# tarjeta-v8.net
KiCad netlist of a schematic drawn in EAGLE
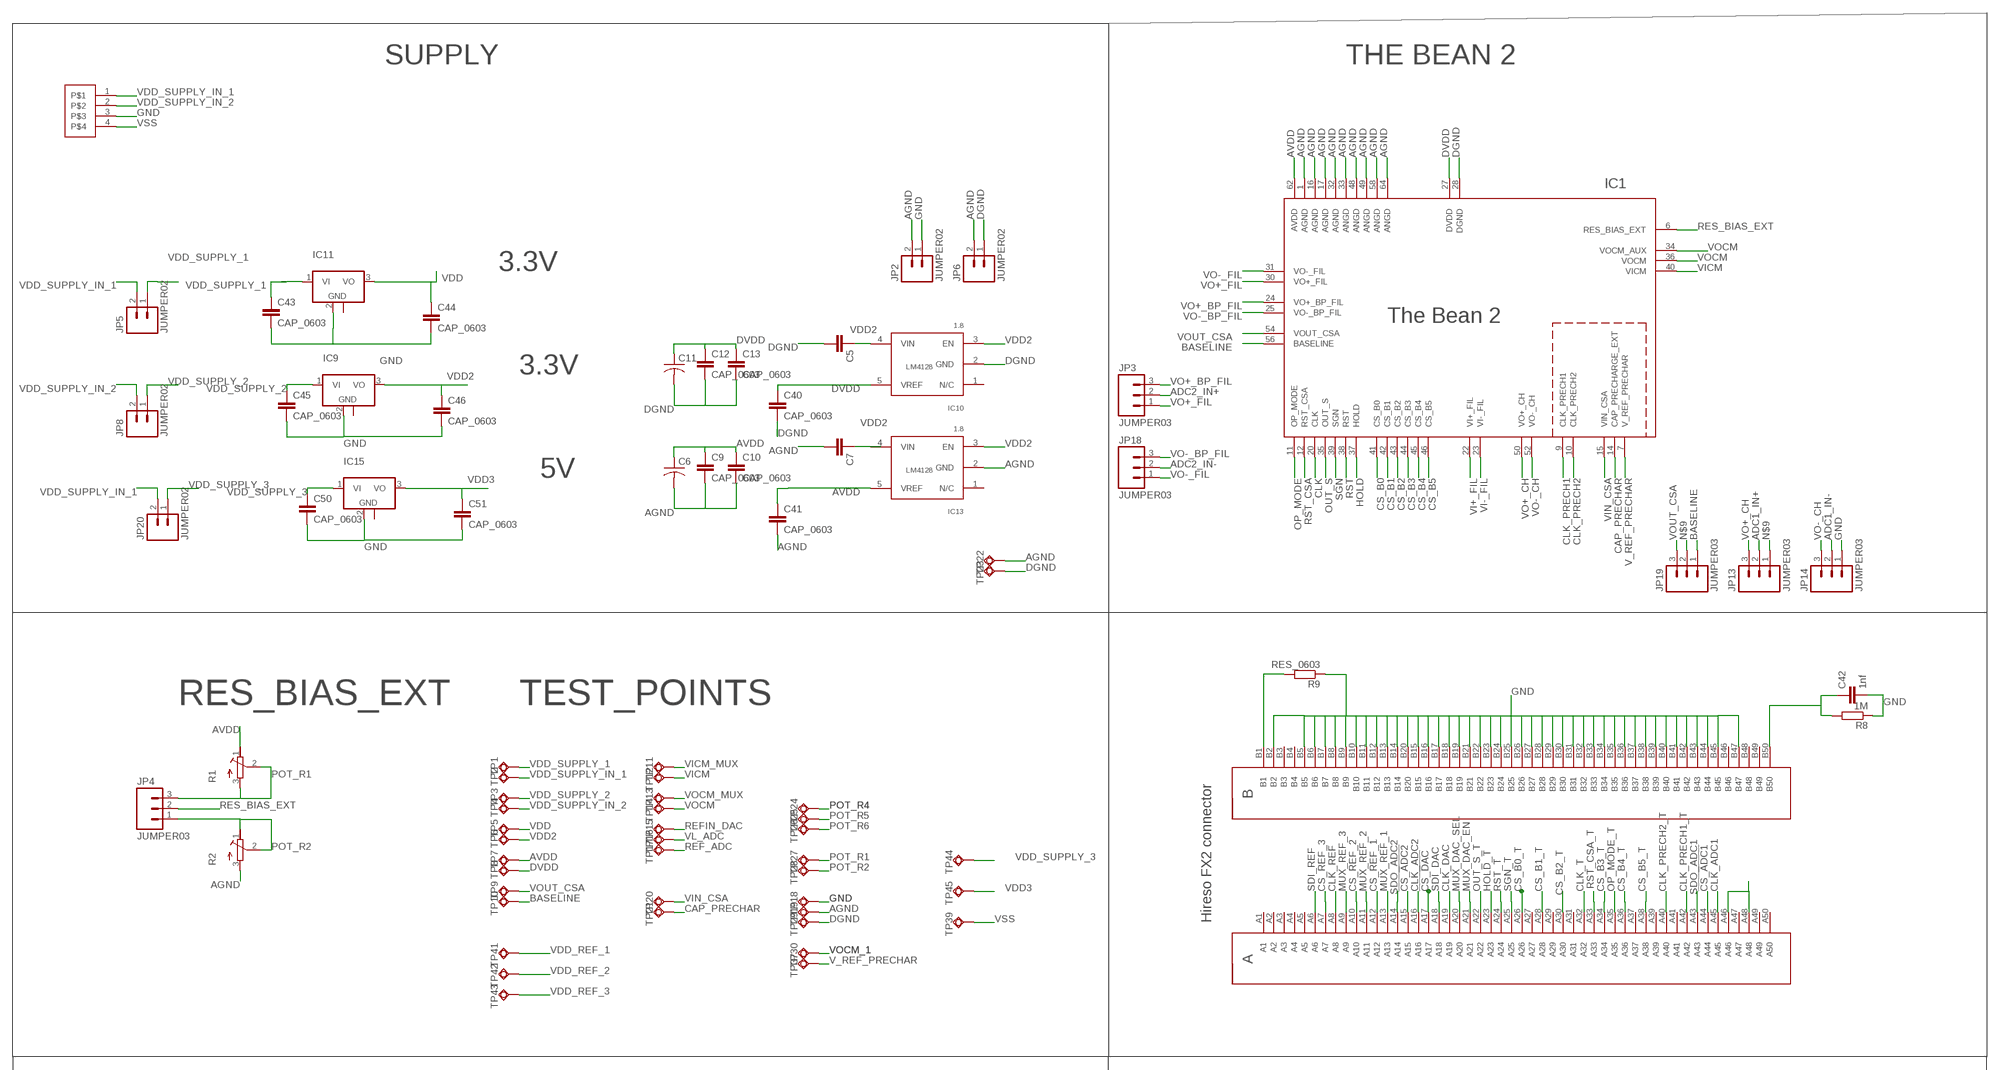
[diagram p0: schematic, sheet 1, part 1 of 3]
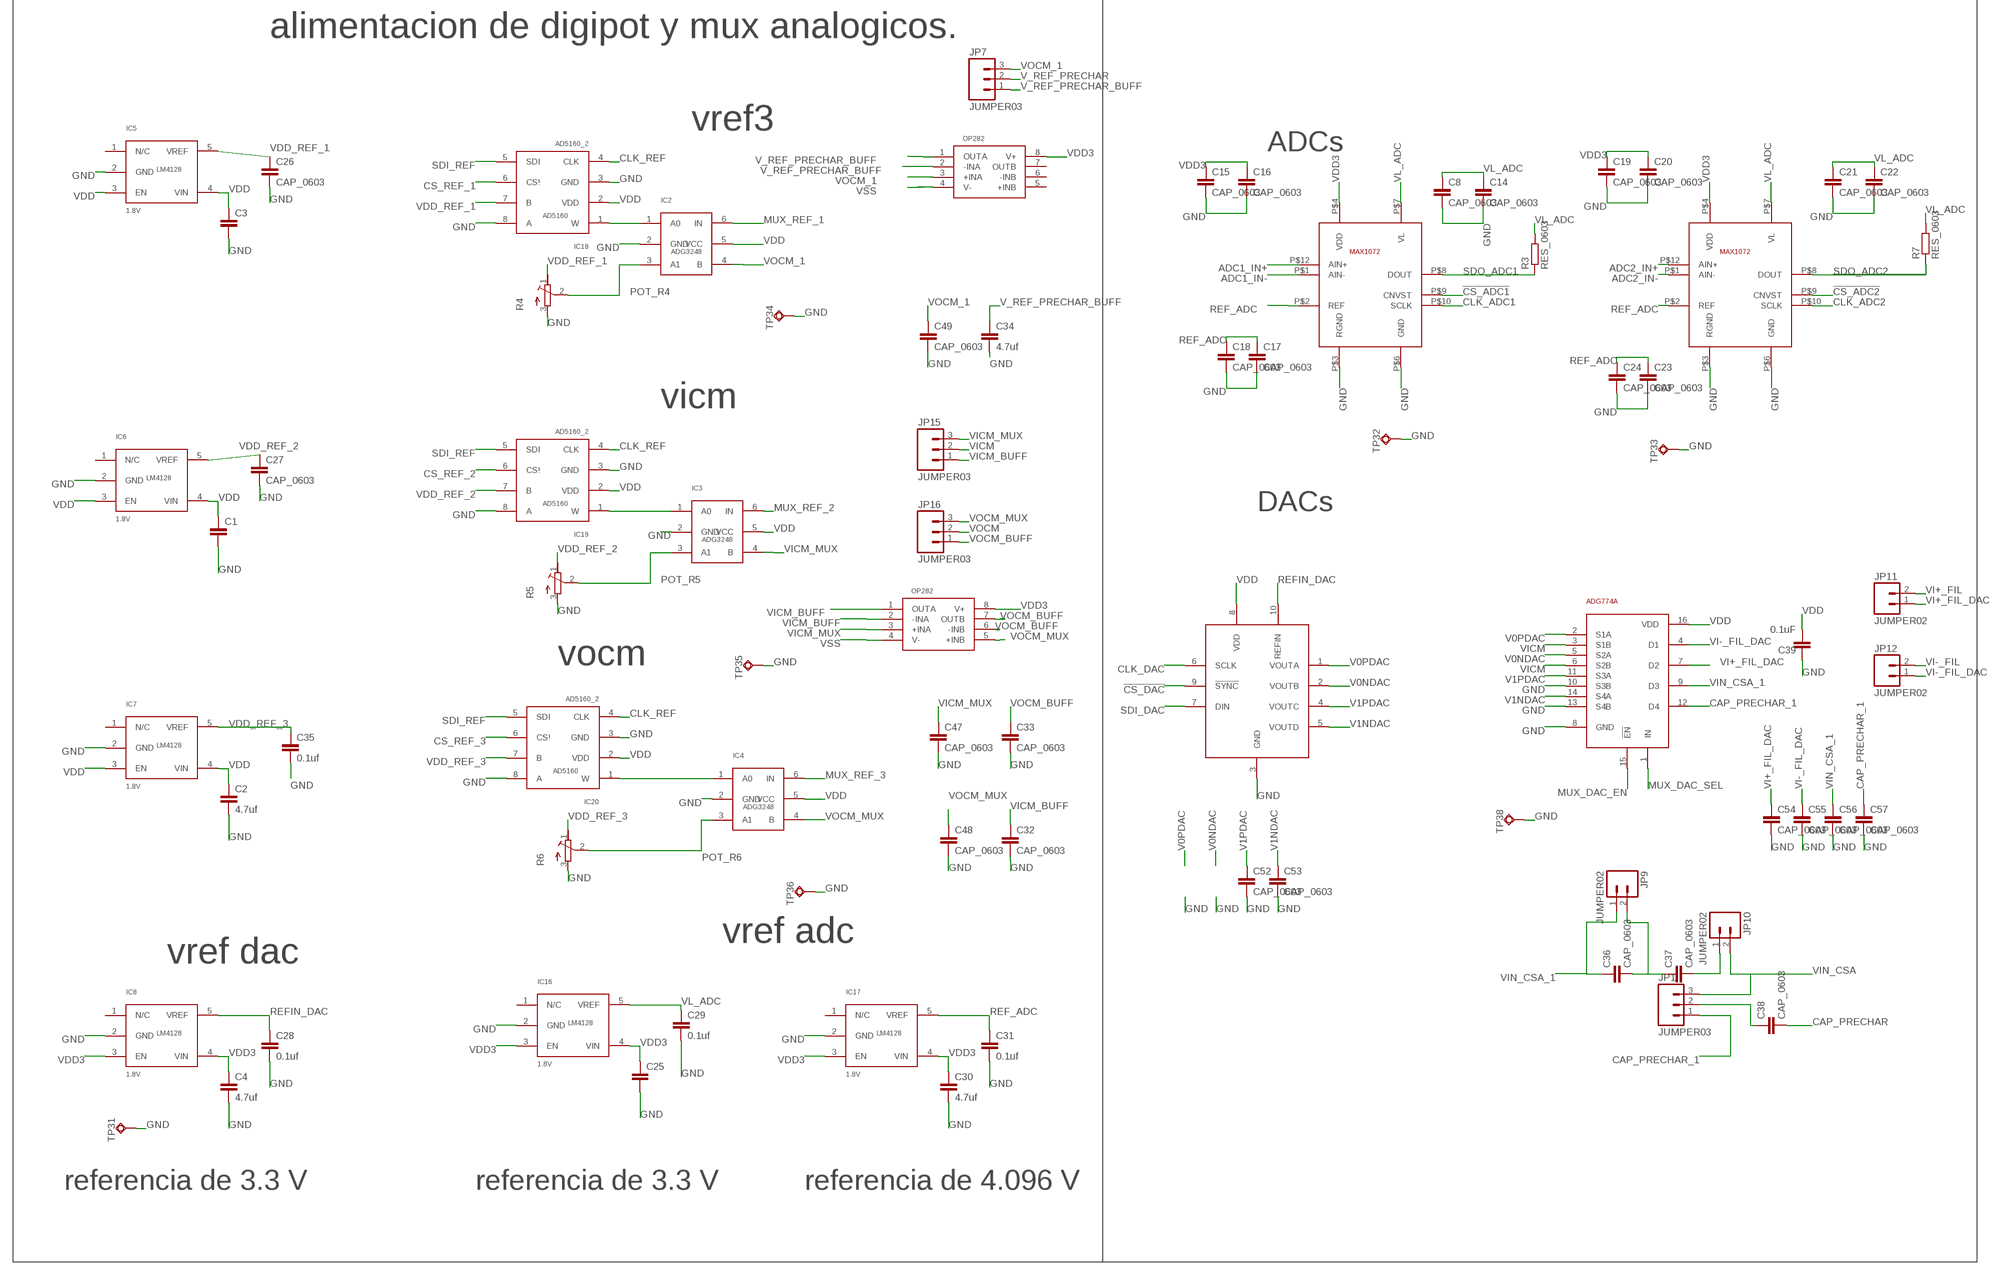
[diagram p1: schematic, sheet 1, part 2 of 3]
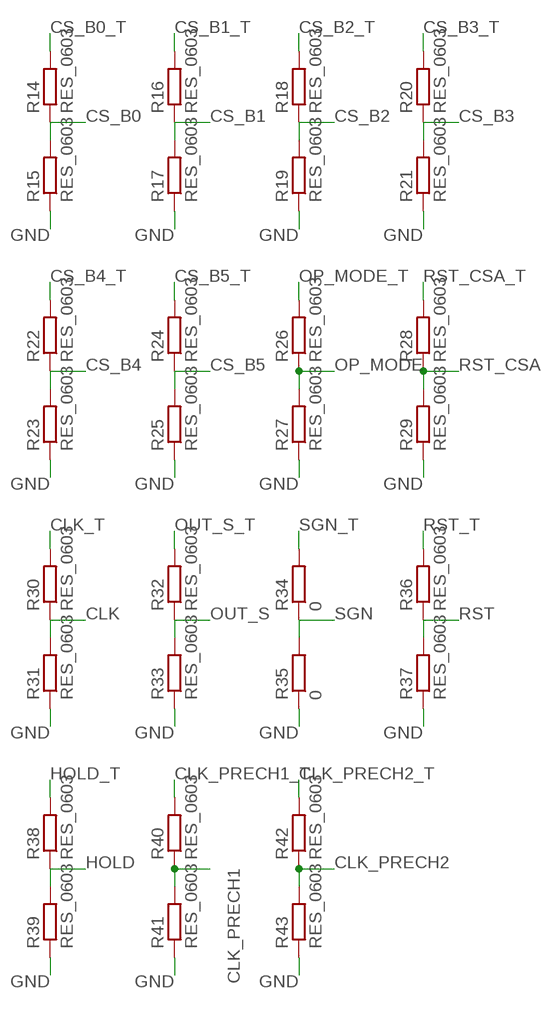
[diagram p2: schematic, sheet 1, part 3 of 3]

(export (version "E")
  (design (tool "Eeschema 10.0.6"))
  (components
    (comp (ref "C1")
      (value "CAP_0402")
      (footprint "eagle-import:C0402")
      (libsource (lib "eagle-import") (part "CAP_0402"))
    )
    (comp (ref "C2")
      (value "4.7uf")
      (footprint "eagle-import:C0402")
      (libsource (lib "eagle-import") (part "CAP_0402"))
    )
    (comp (ref "C3")
      (value "CAP_0402")
      (footprint "eagle-import:C0402")
      (libsource (lib "eagle-import") (part "CAP_0402"))
    )
    (comp (ref "C4")
      (value "4.7uf")
      (footprint "eagle-import:C0402")
      (libsource (lib "eagle-import") (part "CAP_0402"))
    )
    (comp (ref "C5")
      (value "CAP_0402")
      (footprint "eagle-import:C0402")
      (libsource (lib "eagle-import") (part "CAP_0402"))
    )
    (comp (ref "C6")
      (value "CAP_0805")
      (footprint "eagle-import:C0805")
      (libsource (lib "eagle-import") (part "CAP_0805"))
    )
    (comp (ref "C7")
      (value "CAP_0402")
      (footprint "eagle-import:C0402")
      (libsource (lib "eagle-import") (part "CAP_0402"))
    )
    (comp (ref "C8")
      (value "CAP_0603")
      (footprint "eagle-import:C0603")
      (libsource (lib "eagle-import") (part "CAP_0603"))
    )
    (comp (ref "C9")
      (value "CAP_0603")
      (footprint "eagle-import:C0603")
      (libsource (lib "eagle-import") (part "CAP_0603"))
    )
    (comp (ref "C10")
      (value "CAP_0603")
      (footprint "eagle-import:C0603")
      (libsource (lib "eagle-import") (part "CAP_0603"))
    )
    (comp (ref "C11")
      (value "CAP_0805")
      (footprint "eagle-import:C0805")
      (libsource (lib "eagle-import") (part "CAP_0805"))
    )
    (comp (ref "C12")
      (value "CAP_0603")
      (footprint "eagle-import:C0603")
      (libsource (lib "eagle-import") (part "CAP_0603"))
    )
    (comp (ref "C13")
      (value "CAP_0603")
      (footprint "eagle-import:C0603")
      (libsource (lib "eagle-import") (part "CAP_0603"))
    )
    (comp (ref "C14")
      (value "CAP_0603")
      (footprint "eagle-import:C0603")
      (libsource (lib "eagle-import") (part "CAP_0603"))
    )
    (comp (ref "C15")
      (value "CAP_0603")
      (footprint "eagle-import:C0603")
      (libsource (lib "eagle-import") (part "CAP_0603"))
    )
    (comp (ref "C16")
      (value "CAP_0603")
      (footprint "eagle-import:C0603")
      (libsource (lib "eagle-import") (part "CAP_0603"))
    )
    (comp (ref "C17")
      (value "CAP_0603")
      (footprint "eagle-import:C0603")
      (libsource (lib "eagle-import") (part "CAP_0603"))
    )
    (comp (ref "C18")
      (value "CAP_0603")
      (footprint "eagle-import:C0603")
      (libsource (lib "eagle-import") (part "CAP_0603"))
    )
    (comp (ref "C19")
      (value "CAP_0603")
      (footprint "eagle-import:C0603")
      (libsource (lib "eagle-import") (part "CAP_0603"))
    )
    (comp (ref "C20")
      (value "CAP_0603")
      (footprint "eagle-import:C0603")
      (libsource (lib "eagle-import") (part "CAP_0603"))
    )
    (comp (ref "C21")
      (value "CAP_0603")
      (footprint "eagle-import:C0603")
      (libsource (lib "eagle-import") (part "CAP_0603"))
    )
    (comp (ref "C22")
      (value "CAP_0603")
      (footprint "eagle-import:C0603")
      (libsource (lib "eagle-import") (part "CAP_0603"))
    )
    (comp (ref "C23")
      (value "CAP_0603")
      (footprint "eagle-import:C0603")
      (libsource (lib "eagle-import") (part "CAP_0603"))
    )
    (comp (ref "C24")
      (value "CAP_0603")
      (footprint "eagle-import:C0603")
      (libsource (lib "eagle-import") (part "CAP_0603"))
    )
    (comp (ref "C25")
      (value "CAP_0402")
      (footprint "eagle-import:C0402")
      (libsource (lib "eagle-import") (part "CAP_0402"))
    )
    (comp (ref "C26")
      (value "CAP_0603")
      (footprint "eagle-import:C0603")
      (libsource (lib "eagle-import") (part "CAP_0603"))
    )
    (comp (ref "C27")
      (value "CAP_0603")
      (footprint "eagle-import:C0603")
      (libsource (lib "eagle-import") (part "CAP_0603"))
    )
    (comp (ref "C28")
      (value "0.1uf")
      (footprint "eagle-import:C0603")
      (libsource (lib "eagle-import") (part "CAP_0603"))
    )
    (comp (ref "C29")
      (value "0.1uf")
      (footprint "eagle-import:C0603")
      (libsource (lib "eagle-import") (part "CAP_0603"))
    )
    (comp (ref "C30")
      (value "4.7uf")
      (footprint "eagle-import:C0402")
      (libsource (lib "eagle-import") (part "CAP_0402"))
    )
    (comp (ref "C31")
      (value "0.1uf")
      (footprint "eagle-import:C0603")
      (libsource (lib "eagle-import") (part "CAP_0603"))
    )
    (comp (ref "C32")
      (value "CAP_0603")
      (footprint "eagle-import:C0603")
      (libsource (lib "eagle-import") (part "CAP_0603"))
    )
    (comp (ref "C33")
      (value "CAP_0603")
      (footprint "eagle-import:C0603")
      (libsource (lib "eagle-import") (part "CAP_0603"))
    )
    (comp (ref "C34")
      (value "4.7uf")
      (footprint "eagle-import:C0603")
      (libsource (lib "eagle-import") (part "CAP_0603"))
    )
    (comp (ref "C35")
      (value "0.1uf")
      (footprint "eagle-import:C0603")
      (libsource (lib "eagle-import") (part "CAP_0603"))
    )
    (comp (ref "C36")
      (value "CAP_0603")
      (footprint "eagle-import:C0603")
      (libsource (lib "eagle-import") (part "CAP_0603"))
    )
    (comp (ref "C37")
      (value "CAP_0603")
      (footprint "eagle-import:C0603")
      (libsource (lib "eagle-import") (part "CAP_0603"))
    )
    (comp (ref "C38")
      (value "CAP_0603")
      (footprint "eagle-import:C0603")
      (libsource (lib "eagle-import") (part "CAP_0603"))
    )
    (comp (ref "C39")
      (value "0.1uF")
      (footprint "eagle-import:C0603")
      (libsource (lib "eagle-import") (part "CAP_0603"))
    )
    (comp (ref "C40")
      (value "CAP_0603")
      (footprint "eagle-import:C0603")
      (libsource (lib "eagle-import") (part "CAP_0603"))
    )
    (comp (ref "C41")
      (value "CAP_0603")
      (footprint "eagle-import:C0603")
      (libsource (lib "eagle-import") (part "CAP_0603"))
    )
    (comp (ref "C42")
      (value "1nf")
      (footprint "eagle-import:C0603")
      (libsource (lib "eagle-import") (part "CAP_0603"))
    )
    (comp (ref "C43")
      (value "CAP_0603")
      (footprint "eagle-import:C0603")
      (libsource (lib "eagle-import") (part "CAP_0603"))
    )
    (comp (ref "C44")
      (value "CAP_0603")
      (footprint "eagle-import:C0603")
      (libsource (lib "eagle-import") (part "CAP_0603"))
    )
    (comp (ref "C45")
      (value "CAP_0603")
      (footprint "eagle-import:C0603")
      (libsource (lib "eagle-import") (part "CAP_0603"))
    )
    (comp (ref "C46")
      (value "CAP_0603")
      (footprint "eagle-import:C0603")
      (libsource (lib "eagle-import") (part "CAP_0603"))
    )
    (comp (ref "C47")
      (value "CAP_0603")
      (footprint "eagle-import:C0603")
      (libsource (lib "eagle-import") (part "CAP_0603"))
    )
    (comp (ref "C48")
      (value "CAP_0603")
      (footprint "eagle-import:C0603")
      (libsource (lib "eagle-import") (part "CAP_0603"))
    )
    (comp (ref "C49")
      (value "CAP_0603")
      (footprint "eagle-import:C0603")
      (libsource (lib "eagle-import") (part "CAP_0603"))
    )
    (comp (ref "C50")
      (value "CAP_0603")
      (footprint "eagle-import:C0603")
      (libsource (lib "eagle-import") (part "CAP_0603"))
    )
    (comp (ref "C51")
      (value "CAP_0603")
      (footprint "eagle-import:C0603")
      (libsource (lib "eagle-import") (part "CAP_0603"))
    )
    (comp (ref "C52")
      (value "CAP_0603")
      (footprint "eagle-import:C0603")
      (libsource (lib "eagle-import") (part "CAP_0603"))
    )
    (comp (ref "C53")
      (value "CAP_0603")
      (footprint "eagle-import:C0603")
      (libsource (lib "eagle-import") (part "CAP_0603"))
    )
    (comp (ref "C54")
      (value "CAP_0603")
      (footprint "eagle-import:C0603")
      (libsource (lib "eagle-import") (part "CAP_0603"))
    )
    (comp (ref "C55")
      (value "CAP_0603")
      (footprint "eagle-import:C0603")
      (libsource (lib "eagle-import") (part "CAP_0603"))
    )
    (comp (ref "C56")
      (value "CAP_0603")
      (footprint "eagle-import:C0603")
      (libsource (lib "eagle-import") (part "CAP_0603"))
    )
    (comp (ref "C57")
      (value "CAP_0603")
      (footprint "eagle-import:C0603")
      (libsource (lib "eagle-import") (part "CAP_0603"))
    )
    (comp (ref "IC1")
      (value "THE_BEAN_2")
      (footprint "eagle-import:QFN64")
      (libsource (lib "eagle-import") (part "THE_BEAN_2"))
    )
    (comp (ref "IC2")
      (value "ADG3248")
      (footprint "eagle-import:SC70")
      (libsource (lib "eagle-import") (part "ADG3248"))
    )
    (comp (ref "IC3")
      (value "ADG3248")
      (footprint "eagle-import:SC70")
      (libsource (lib "eagle-import") (part "ADG3248"))
    )
    (comp (ref "IC4")
      (value "ADG3248")
      (footprint "eagle-import:SC70")
      (libsource (lib "eagle-import") (part "ADG3248"))
    )
    (comp (ref "IC5")
      (value "1.8V")
      (footprint "eagle-import:SOT23-5L_2")
      (libsource (lib "eagle-import") (part "LM4128_2"))
    )
    (comp (ref "IC6")
      (value "1.8V")
      (footprint "eagle-import:SOT23-5L_2")
      (libsource (lib "eagle-import") (part "LM4128_2"))
    )
    (comp (ref "IC7")
      (value "1.8V")
      (footprint "eagle-import:SOT23-5L_2")
      (libsource (lib "eagle-import") (part "LM4128_2"))
    )
    (comp (ref "IC8")
      (value "1.8V")
      (footprint "eagle-import:SOT23-5L_2")
      (libsource (lib "eagle-import") (part "LM4128_2"))
    )
    (comp (ref "IC9")
      (value "UA78M33DCY")
      (footprint "eagle-import:SOT223")
      (libsource (lib "eagle-import") (part "UA78MDCY33"))
    )
    (comp (ref "IC10")
      (value "1.8")
      (footprint "eagle-import:SOT23-5L_2")
      (libsource (lib "eagle-import") (part "LM4128_2"))
    )
    (comp (ref "IC11")
      (value "UA78M33DCY")
      (footprint "eagle-import:SOT223")
      (libsource (lib "eagle-import") (part "UA78MDCY33"))
    )
    (comp (ref "IC12")
      (value "OP282")
      (footprint "eagle-import:MSOP8")
      (libsource (lib "eagle-import") (part "OP282"))
    )
    (comp (ref "IC13")
      (value "1.8")
      (footprint "eagle-import:SOT23-5L_2")
      (libsource (lib "eagle-import") (part "LM4128_2"))
    )
    (comp (ref "IC14")
      (value "OP282")
      (footprint "eagle-import:MSOP8")
      (libsource (lib "eagle-import") (part "OP282"))
    )
    (comp (ref "IC15")
      (value "UA78M33DCY")
      (footprint "eagle-import:SOT223")
      (libsource (lib "eagle-import") (part "UA78MDCY33"))
    )
    (comp (ref "IC16")
      (value "1.8V")
      (footprint "eagle-import:SOT23-5L_2")
      (libsource (lib "eagle-import") (part "LM4128_2"))
    )
    (comp (ref "IC17")
      (value "1.8V")
      (footprint "eagle-import:SOT23-5L_2")
      (libsource (lib "eagle-import") (part "LM4128_2"))
    )
    (comp (ref "IC18")
      (value "AD5160_2")
      (footprint "eagle-import:SOT23-8_2")
      (libsource (lib "eagle-import") (part "AD5160_2"))
    )
    (comp (ref "IC19")
      (value "AD5160_2")
      (footprint "eagle-import:SOT23-8_2")
      (libsource (lib "eagle-import") (part "AD5160_2"))
    )
    (comp (ref "IC20")
      (value "AD5160_2")
      (footprint "eagle-import:SOT23-8_2")
      (libsource (lib "eagle-import") (part "AD5160_2"))
    )
    (comp (ref "IC21")
      (value "ADG774A")
      (footprint "eagle-import:QSOP16")
      (libsource (lib "eagle-import") (part "ADG774A"))
    )
    (comp (ref "IC22")
      (value "MAX1072")
      (footprint "eagle-import:TQFN12")
      (libsource (lib "eagle-import") (part "MAX1072"))
    )
    (comp (ref "IC23")
      (value "DAC7554")
      (footprint "eagle-import:MSOP10")
      (libsource (lib "eagle-import") (part "DAC7554"))
    )
    (comp (ref "J1")
      (value "HIRESO_FX_CONNECTOR")
      (footprint "eagle-import:FX2-100S-1.27")
      (libsource (lib "eagle-import") (part "HIRESO_FX_CONNECTOR"))
    )
    (comp (ref "JP1")
      (value "JUMPER03")
      (footprint "eagle-import:1X03")
      (libsource (lib "eagle-import") (part "JUMPER03"))
    )
    (comp (ref "JP2")
      (value "JUMPER02")
      (footprint "eagle-import:1X02")
      (libsource (lib "eagle-import") (part "JUMPER02"))
    )
    (comp (ref "JP3")
      (value "JUMPER03")
      (footprint "eagle-import:1X03")
      (libsource (lib "eagle-import") (part "JUMPER03"))
    )
    (comp (ref "JP4")
      (value "JUMPER03")
      (footprint "eagle-import:1X03")
      (libsource (lib "eagle-import") (part "JUMPER03"))
    )
    (comp (ref "JP5")
      (value "JUMPER02")
      (footprint "eagle-import:1X02")
      (libsource (lib "eagle-import") (part "JUMPER02"))
    )
    (comp (ref "JP6")
      (value "JUMPER02")
      (footprint "eagle-import:1X02")
      (libsource (lib "eagle-import") (part "JUMPER02"))
    )
    (comp (ref "JP7")
      (value "JUMPER03")
      (footprint "eagle-import:1X03")
      (libsource (lib "eagle-import") (part "JUMPER03"))
    )
    (comp (ref "JP8")
      (value "JUMPER02")
      (footprint "eagle-import:1X02")
      (libsource (lib "eagle-import") (part "JUMPER02"))
    )
    (comp (ref "JP9")
      (value "JUMPER02")
      (footprint "eagle-import:1X02")
      (libsource (lib "eagle-import") (part "JUMPER02"))
    )
    (comp (ref "JP10")
      (value "JUMPER02")
      (footprint "eagle-import:1X02")
      (libsource (lib "eagle-import") (part "JUMPER02"))
    )
    (comp (ref "JP11")
      (value "JUMPER02")
      (footprint "eagle-import:1X02")
      (libsource (lib "eagle-import") (part "JUMPER02"))
    )
    (comp (ref "JP12")
      (value "JUMPER02")
      (footprint "eagle-import:1X02")
      (libsource (lib "eagle-import") (part "JUMPER02"))
    )
    (comp (ref "JP13")
      (value "JUMPER03")
      (footprint "eagle-import:1X03")
      (libsource (lib "eagle-import") (part "JUMPER03"))
    )
    (comp (ref "JP14")
      (value "JUMPER03")
      (footprint "eagle-import:1X03")
      (libsource (lib "eagle-import") (part "JUMPER03"))
    )
    (comp (ref "JP15")
      (value "JUMPER03")
      (footprint "eagle-import:1X03")
      (libsource (lib "eagle-import") (part "JUMPER03"))
    )
    (comp (ref "JP16")
      (value "JUMPER03")
      (footprint "eagle-import:1X03")
      (libsource (lib "eagle-import") (part "JUMPER03"))
    )
    (comp (ref "JP17")
      (value "JUMPER04")
      (footprint "eagle-import:1X04")
      (libsource (lib "eagle-import") (part "JUMPER04"))
    )
    (comp (ref "JP18")
      (value "JUMPER03")
      (footprint "eagle-import:1X03")
      (libsource (lib "eagle-import") (part "JUMPER03"))
    )
    (comp (ref "JP19")
      (value "JUMPER03")
      (footprint "eagle-import:1X03")
      (libsource (lib "eagle-import") (part "JUMPER03"))
    )
    (comp (ref "JP20")
      (value "JUMPER02")
      (footprint "eagle-import:1X02")
      (libsource (lib "eagle-import") (part "JUMPER02"))
    )
    (comp (ref "R1")
      (value "TRIMMER_ST5")
      (footprint "eagle-import:ST-5EW")
      (libsource (lib "eagle-import") (part "TRIMMER_ST5"))
    )
    (comp (ref "R2")
      (value "TRIMMER_ST5")
      (footprint "eagle-import:ST-5EW")
      (libsource (lib "eagle-import") (part "TRIMMER_ST5"))
    )
    (comp (ref "R3")
      (value "RES_0603")
      (footprint "eagle-import:R0603")
      (libsource (lib "eagle-import") (part "RES_0603"))
    )
    (comp (ref "R4")
      (value "TRIMMER_ST5")
      (footprint "eagle-import:ST-5EW")
      (libsource (lib "eagle-import") (part "TRIMMER_ST5"))
    )
    (comp (ref "R5")
      (value "TRIMMER_ST5")
      (footprint "eagle-import:ST-5EW")
      (libsource (lib "eagle-import") (part "TRIMMER_ST5"))
    )
    (comp (ref "R6")
      (value "TRIMMER_ST5")
      (footprint "eagle-import:ST-5EW")
      (libsource (lib "eagle-import") (part "TRIMMER_ST5"))
    )
    (comp (ref "R7")
      (value "RES_0603")
      (footprint "eagle-import:R0603")
      (libsource (lib "eagle-import") (part "RES_0603"))
    )
    (comp (ref "R8")
      (value "1M")
      (footprint "eagle-import:R0603")
      (libsource (lib "eagle-import") (part "RES_0603"))
    )
    (comp (ref "R9")
      (value "RES_0603")
      (footprint "eagle-import:R0603")
      (libsource (lib "eagle-import") (part "RES_0603"))
    )
    (comp (ref "R14")
      (value "RES_0603")
      (footprint "eagle-import:R0603")
      (libsource (lib "eagle-import") (part "RES_0603"))
    )
    (comp (ref "R15")
      (value "RES_0603")
      (footprint "eagle-import:R0603")
      (libsource (lib "eagle-import") (part "RES_0603"))
    )
    (comp (ref "R16")
      (value "RES_0603")
      (footprint "eagle-import:R0603")
      (libsource (lib "eagle-import") (part "RES_0603"))
    )
    (comp (ref "R17")
      (value "RES_0603")
      (footprint "eagle-import:R0603")
      (libsource (lib "eagle-import") (part "RES_0603"))
    )
    (comp (ref "R18")
      (value "RES_0603")
      (footprint "eagle-import:R0603")
      (libsource (lib "eagle-import") (part "RES_0603"))
    )
    (comp (ref "R19")
      (value "RES_0603")
      (footprint "eagle-import:R0603")
      (libsource (lib "eagle-import") (part "RES_0603"))
    )
    (comp (ref "R20")
      (value "RES_0603")
      (footprint "eagle-import:R0603")
      (libsource (lib "eagle-import") (part "RES_0603"))
    )
    (comp (ref "R21")
      (value "RES_0603")
      (footprint "eagle-import:R0603")
      (libsource (lib "eagle-import") (part "RES_0603"))
    )
    (comp (ref "R22")
      (value "RES_0603")
      (footprint "eagle-import:R0603")
      (libsource (lib "eagle-import") (part "RES_0603"))
    )
    (comp (ref "R23")
      (value "RES_0603")
      (footprint "eagle-import:R0603")
      (libsource (lib "eagle-import") (part "RES_0603"))
    )
    (comp (ref "R24")
      (value "RES_0603")
      (footprint "eagle-import:R0603")
      (libsource (lib "eagle-import") (part "RES_0603"))
    )
    (comp (ref "R25")
      (value "RES_0603")
      (footprint "eagle-import:R0603")
      (libsource (lib "eagle-import") (part "RES_0603"))
    )
    (comp (ref "R26")
      (value "RES_0603")
      (footprint "eagle-import:R0603")
      (libsource (lib "eagle-import") (part "RES_0603"))
    )
    (comp (ref "R27")
      (value "RES_0603")
      (footprint "eagle-import:R0603")
      (libsource (lib "eagle-import") (part "RES_0603"))
    )
    (comp (ref "R28")
      (value "RES_0603")
      (footprint "eagle-import:R0603")
      (libsource (lib "eagle-import") (part "RES_0603"))
    )
    (comp (ref "R29")
      (value "RES_0603")
      (footprint "eagle-import:R0603")
      (libsource (lib "eagle-import") (part "RES_0603"))
    )
    (comp (ref "R30")
      (value "RES_0603")
      (footprint "eagle-import:R0603")
      (libsource (lib "eagle-import") (part "RES_0603"))
    )
    (comp (ref "R31")
      (value "RES_0603")
      (footprint "eagle-import:R0603")
      (libsource (lib "eagle-import") (part "RES_0603"))
    )
    (comp (ref "R32")
      (value "RES_0603")
      (footprint "eagle-import:R0603")
      (libsource (lib "eagle-import") (part "RES_0603"))
    )
    (comp (ref "R33")
      (value "RES_0603")
      (footprint "eagle-import:R0603")
      (libsource (lib "eagle-import") (part "RES_0603"))
    )
    (comp (ref "R34")
      (value "0")
      (footprint "eagle-import:R0603")
      (libsource (lib "eagle-import") (part "RES_0603"))
    )
    (comp (ref "R35")
      (value "0")
      (footprint "eagle-import:R0603")
      (libsource (lib "eagle-import") (part "RES_0603"))
    )
    (comp (ref "R36")
      (value "RES_0603")
      (footprint "eagle-import:R0603")
      (libsource (lib "eagle-import") (part "RES_0603"))
    )
    (comp (ref "R37")
      (value "RES_0603")
      (footprint "eagle-import:R0603")
      (libsource (lib "eagle-import") (part "RES_0603"))
    )
    (comp (ref "R38")
      (value "RES_0603")
      (footprint "eagle-import:R0603")
      (libsource (lib "eagle-import") (part "RES_0603"))
    )
    (comp (ref "R39")
      (value "RES_0603")
      (footprint "eagle-import:R0603")
      (libsource (lib "eagle-import") (part "RES_0603"))
    )
    (comp (ref "R40")
      (value "RES_0603")
      (footprint "eagle-import:R0603")
      (libsource (lib "eagle-import") (part "RES_0603"))
    )
    (comp (ref "R41")
      (value "RES_0603")
      (footprint "eagle-import:R0603")
      (libsource (lib "eagle-import") (part "RES_0603"))
    )
    (comp (ref "R42")
      (value "RES_0603")
      (footprint "eagle-import:R0603")
      (libsource (lib "eagle-import") (part "RES_0603"))
    )
    (comp (ref "R43")
      (value "RES_0603")
      (footprint "eagle-import:R0603")
      (libsource (lib "eagle-import") (part "RES_0603"))
    )
    (comp (ref "TP1")
      (value "TEST_POINT")
      (footprint "eagle-import:TP")
      (libsource (lib "eagle-import") (part "TEST_POINT"))
    )
    (comp (ref "TP2")
      (value "TEST_POINT")
      (footprint "eagle-import:TP")
      (libsource (lib "eagle-import") (part "TEST_POINT"))
    )
    (comp (ref "TP3")
      (value "TEST_POINT")
      (footprint "eagle-import:TP")
      (libsource (lib "eagle-import") (part "TEST_POINT"))
    )
    (comp (ref "TP4")
      (value "TEST_POINT")
      (footprint "eagle-import:TP")
      (libsource (lib "eagle-import") (part "TEST_POINT"))
    )
    (comp (ref "TP5")
      (value "TEST_POINT")
      (footprint "eagle-import:TP")
      (libsource (lib "eagle-import") (part "TEST_POINT"))
    )
    (comp (ref "TP6")
      (value "TEST_POINT")
      (footprint "eagle-import:TP")
      (libsource (lib "eagle-import") (part "TEST_POINT"))
    )
    (comp (ref "TP7")
      (value "TEST_POINT")
      (footprint "eagle-import:TP")
      (libsource (lib "eagle-import") (part "TEST_POINT"))
    )
    (comp (ref "TP8")
      (value "TEST_POINT")
      (footprint "eagle-import:TP")
      (libsource (lib "eagle-import") (part "TEST_POINT"))
    )
    (comp (ref "TP9")
      (value "TEST_POINT")
      (footprint "eagle-import:TP")
      (libsource (lib "eagle-import") (part "TEST_POINT"))
    )
    (comp (ref "TP10")
      (value "TEST_POINT")
      (footprint "eagle-import:TP")
      (libsource (lib "eagle-import") (part "TEST_POINT"))
    )
    (comp (ref "TP11")
      (value "TEST_POINT")
      (footprint "eagle-import:TP")
      (libsource (lib "eagle-import") (part "TEST_POINT"))
    )
    (comp (ref "TP12")
      (value "TEST_POINT")
      (footprint "eagle-import:TP")
      (libsource (lib "eagle-import") (part "TEST_POINT"))
    )
    (comp (ref "TP13")
      (value "TEST_POINT")
      (footprint "eagle-import:TP")
      (libsource (lib "eagle-import") (part "TEST_POINT"))
    )
    (comp (ref "TP14")
      (value "TEST_POINT")
      (footprint "eagle-import:TP")
      (libsource (lib "eagle-import") (part "TEST_POINT"))
    )
    (comp (ref "TP15")
      (value "TEST_POINT")
      (footprint "eagle-import:TP")
      (libsource (lib "eagle-import") (part "TEST_POINT"))
    )
    (comp (ref "TP16")
      (value "TEST_POINT")
      (footprint "eagle-import:TP")
      (libsource (lib "eagle-import") (part "TEST_POINT"))
    )
    (comp (ref "TP17")
      (value "TEST_POINT")
      (footprint "eagle-import:TP")
      (libsource (lib "eagle-import") (part "TEST_POINT"))
    )
    (comp (ref "TP18")
      (value "TEST_POINT")
      (footprint "eagle-import:TP")
      (libsource (lib "eagle-import") (part "TEST_POINT"))
    )
    (comp (ref "TP19")
      (value "TEST_POINT")
      (footprint "eagle-import:TP")
      (libsource (lib "eagle-import") (part "TEST_POINT"))
    )
    (comp (ref "TP20")
      (value "TEST_POINT")
      (footprint "eagle-import:TP")
      (libsource (lib "eagle-import") (part "TEST_POINT"))
    )
    (comp (ref "TP21")
      (value "TEST_POINT")
      (footprint "eagle-import:TP")
      (libsource (lib "eagle-import") (part "TEST_POINT"))
    )
    (comp (ref "TP22")
      (value "TEST_POINT")
      (footprint "eagle-import:TP")
      (libsource (lib "eagle-import") (part "TEST_POINT"))
    )
    (comp (ref "TP23")
      (value "TEST_POINT")
      (footprint "eagle-import:TP")
      (libsource (lib "eagle-import") (part "TEST_POINT"))
    )
    (comp (ref "TP24")
      (value "TEST_POINT")
      (footprint "eagle-import:TP")
      (libsource (lib "eagle-import") (part "TEST_POINT"))
    )
    (comp (ref "TP25")
      (value "TEST_POINT")
      (footprint "eagle-import:TP")
      (libsource (lib "eagle-import") (part "TEST_POINT"))
    )
    (comp (ref "TP26")
      (value "TEST_POINT")
      (footprint "eagle-import:TP")
      (libsource (lib "eagle-import") (part "TEST_POINT"))
    )
    (comp (ref "TP27")
      (value "TEST_POINT")
      (footprint "eagle-import:TP")
      (libsource (lib "eagle-import") (part "TEST_POINT"))
    )
    (comp (ref "TP28")
      (value "TEST_POINT")
      (footprint "eagle-import:TP")
      (libsource (lib "eagle-import") (part "TEST_POINT"))
    )
    (comp (ref "TP29")
      (value "TEST_POINT")
      (footprint "eagle-import:TP")
      (libsource (lib "eagle-import") (part "TEST_POINT"))
    )
    (comp (ref "TP30")
      (value "TEST_POINT")
      (footprint "eagle-import:TP")
      (libsource (lib "eagle-import") (part "TEST_POINT"))
    )
    (comp (ref "TP31")
      (value "TEST_POINT")
      (footprint "eagle-import:TP")
      (libsource (lib "eagle-import") (part "TEST_POINT"))
    )
    (comp (ref "TP32")
      (value "TEST_POINT")
      (footprint "eagle-import:TP")
      (libsource (lib "eagle-import") (part "TEST_POINT"))
    )
    (comp (ref "TP33")
      (value "TEST_POINT")
      (footprint "eagle-import:TP")
      (libsource (lib "eagle-import") (part "TEST_POINT"))
    )
    (comp (ref "TP34")
      (value "TEST_POINT")
      (footprint "eagle-import:TP")
      (libsource (lib "eagle-import") (part "TEST_POINT"))
    )
    (comp (ref "TP35")
      (value "TEST_POINT")
      (footprint "eagle-import:TP")
      (libsource (lib "eagle-import") (part "TEST_POINT"))
    )
    (comp (ref "TP36")
      (value "TEST_POINT")
      (footprint "eagle-import:TP")
      (libsource (lib "eagle-import") (part "TEST_POINT"))
    )
    (comp (ref "TP37")
      (value "TEST_POINT")
      (footprint "eagle-import:TP")
      (libsource (lib "eagle-import") (part "TEST_POINT"))
    )
    (comp (ref "TP38")
      (value "TEST_POINT")
      (footprint "eagle-import:TP")
      (libsource (lib "eagle-import") (part "TEST_POINT"))
    )
    (comp (ref "TP39")
      (value "TEST_POINT")
      (footprint "eagle-import:TP")
      (libsource (lib "eagle-import") (part "TEST_POINT"))
    )
    (comp (ref "TP41")
      (value "TEST_POINT")
      (footprint "eagle-import:TP")
      (libsource (lib "eagle-import") (part "TEST_POINT"))
    )
    (comp (ref "TP42")
      (value "TEST_POINT")
      (footprint "eagle-import:TP")
      (libsource (lib "eagle-import") (part "TEST_POINT"))
    )
    (comp (ref "TP43")
      (value "TEST_POINT")
      (footprint "eagle-import:TP")
      (libsource (lib "eagle-import") (part "TEST_POINT"))
    )
    (comp (ref "TP44")
      (value "TEST_POINT")
      (footprint "eagle-import:TP")
      (libsource (lib "eagle-import") (part "TEST_POINT"))
    )
    (comp (ref "TP45")
      (value "TEST_POINT")
      (footprint "eagle-import:TP")
      (libsource (lib "eagle-import") (part "TEST_POINT"))
    )
    (comp (ref "U$5")
      (value "MAX1072")
      (footprint "eagle-import:TQFN12")
      (libsource (lib "eagle-import") (part "MAX1072"))
    )
  )
  (nets
    (net (code "1") (name "/ADC1_IN+") (class "Default")
      (node (ref "IC22") (pin "P$12") (pinfunction "AIN+_P$12") (pintype "bidirectional"))
      (node (ref "JP13") (pin "2") (pinfunction "2_2") (pintype "passive"))
    )
    (net (code "2") (name "/ADC1_IN-") (class "Default")
      (node (ref "IC22") (pin "P$1") (pinfunction "AIN-_P$1") (pintype "bidirectional"))
      (node (ref "JP14") (pin "2") (pinfunction "2_2") (pintype "passive"))
    )
    (net (code "3") (name "/ADC2_IN+") (class "Default")
      (node (ref "JP3") (pin "2") (pinfunction "2_2") (pintype "passive"))
      (node (ref "U$5") (pin "P$12") (pinfunction "AIN+_P$12") (pintype "bidirectional"))
    )
    (net (code "4") (name "/ADC2_IN-") (class "Default")
      (node (ref "JP18") (pin "2") (pinfunction "2_2") (pintype "passive"))
      (node (ref "U$5") (pin "P$1") (pinfunction "AIN-_P$1") (pintype "bidirectional"))
    )
    (net (code "5") (name "/AGND") (class "Default")
      (node (ref "C10") (pin "2") (pinfunction "2_2") (pintype "passive"))
      (node (ref "C41") (pin "2") (pinfunction "2_2") (pintype "passive"))
      (node (ref "C6") (pin "2") (pinfunction "2_2") (pintype "passive"))
      (node (ref "C7") (pin "2") (pinfunction "2_2") (pintype "passive"))
      (node (ref "C9") (pin "2") (pinfunction "2_2") (pintype "passive"))
      (node (ref "IC1") (pin "1") (pinfunction "AGND_1") (pintype "power_in"))
      (node (ref "IC1") (pin "16") (pinfunction "AGND_16") (pintype "power_in"))
      (node (ref "IC1") (pin "17") (pinfunction "AGND_17") (pintype "power_in"))
      (node (ref "IC1") (pin "32") (pinfunction "AGND_32") (pintype "power_in"))
      (node (ref "IC1") (pin "33") (pinfunction "ANGD_33") (pintype "power_in"))
      (node (ref "IC1") (pin "48") (pinfunction "ANGD_48") (pintype "power_in"))
      (node (ref "IC1") (pin "49") (pinfunction "ANGD_49") (pintype "power_in"))
      (node (ref "IC1") (pin "58") (pinfunction "ANGD_58") (pintype "power_in"))
      (node (ref "IC1") (pin "64") (pinfunction "ANGD_64") (pintype "power_in"))
      (node (ref "IC13") (pin "2") (pinfunction "GND_2") (pintype "bidirectional"))
      (node (ref "JP2") (pin "2") (pinfunction "2_2") (pintype "passive"))
      (node (ref "JP6") (pin "2") (pinfunction "2_2") (pintype "passive"))
      (node (ref "R2") (pin "3") (pinfunction "3_3") (pintype "passive"))
      (node (ref "TP19") (pin "TP") (pinfunction "TP_TP") (pintype "input"))
      (node (ref "TP22") (pin "TP") (pinfunction "TP_TP") (pintype "input"))
    )
    (net (code "6") (name "/AVDD") (class "Default")
      (node (ref "C10") (pin "1") (pinfunction "1_1") (pintype "passive"))
      (node (ref "C41") (pin "1") (pinfunction "1_1") (pintype "passive"))
      (node (ref "C6") (pin "1") (pinfunction "1_1") (pintype "passive"))
      (node (ref "C9") (pin "1") (pinfunction "1_1") (pintype "passive"))
      (node (ref "IC1") (pin "62") (pinfunction "AVDD_62") (pintype "power_in"))
      (node (ref "IC13") (pin "5") (pinfunction "VREF_5") (pintype "bidirectional"))
      (node (ref "R1") (pin "1") (pinfunction "1_1") (pintype "passive"))
      (node (ref "TP7") (pin "TP") (pinfunction "TP_TP") (pintype "input"))
    )
    (net (code "7") (name "/BASELINE") (class "Default")
      (node (ref "IC1") (pin "56") (pinfunction "BASELINE_56") (pintype "output"))
      (node (ref "JP19") (pin "1") (pinfunction "1_1") (pintype "passive"))
      (node (ref "TP10") (pin "TP") (pinfunction "TP_TP") (pintype "input"))
    )
    (net (code "8") (name "/CAP_PRECHAR") (class "Default")
      (node (ref "C38") (pin "2") (pinfunction "2_2") (pintype "passive"))
      (node (ref "IC1") (pin "14") (pinfunction "CAP_PRECHARGE_EXT_14") (pintype "input"))
      (node (ref "TP21") (pin "TP") (pinfunction "TP_TP") (pintype "input"))
    )
    (net (code "9") (name "/CAP_PRECHAR_1") (class "Default")
      (node (ref "C57") (pin "1") (pinfunction "1_1") (pintype "passive"))
      (node (ref "IC21") (pin "12") (pinfunction "D4_12") (pintype "bidirectional"))
      (node (ref "JP1") (pin "1") (pinfunction "1_1") (pintype "passive"))
    )
    (net (code "10") (name "/CLK") (class "Default")
      (node (ref "IC1") (pin "20") (pinfunction "CLK_20") (pintype "bidirectional"))
      (node (ref "R30") (pin "1") (pinfunction "1_1") (pintype "passive"))
      (node (ref "R31") (pin "2") (pinfunction "2_2") (pintype "passive"))
    )
    (net (code "11") (name "/CLK_ADC1") (class "Default")
      (node (ref "IC22") (pin "P$10") (pinfunction "SCLK_P$10") (pintype "bidirectional"))
      (node (ref "J1") (pin "A45") (pinfunction "A45_A45") (pintype "bidirectional"))
    )
    (net (code "12") (name "/CLK_ADC2") (class "Default")
      (node (ref "J1") (pin "A16") (pinfunction "A16_A16") (pintype "bidirectional"))
      (node (ref "U$5") (pin "P$10") (pinfunction "SCLK_P$10") (pintype "bidirectional"))
    )
    (net (code "13") (name "/CLK_DAC") (class "Default")
      (node (ref "IC23") (pin "6") (pinfunction "SCLK_6") (pintype "bidirectional"))
      (node (ref "J1") (pin "A19") (pinfunction "A19_A19") (pintype "bidirectional"))
    )
    (net (code "14") (name "/CLK_PRECH1") (class "Default")
      (node (ref "IC1") (pin "9") (pinfunction "CLK_PRECH1_9") (pintype "bidirectional"))
      (node (ref "R40") (pin "1") (pinfunction "1_1") (pintype "passive"))
      (node (ref "R41") (pin "2") (pinfunction "2_2") (pintype "passive"))
    )
    (net (code "15") (name "/CLK_PRECH1_T") (class "Default")
      (node (ref "J1") (pin "A42") (pinfunction "A42_A42") (pintype "bidirectional"))
      (node (ref "R40") (pin "2") (pinfunction "2_2") (pintype "passive"))
    )
    (net (code "16") (name "/CLK_PRECH2") (class "Default")
      (node (ref "IC1") (pin "10") (pinfunction "CLK_PRECH2_10") (pintype "bidirectional"))
      (node (ref "R42") (pin "1") (pinfunction "1_1") (pintype "passive"))
      (node (ref "R43") (pin "2") (pinfunction "2_2") (pintype "passive"))
    )
    (net (code "17") (name "/CLK_PRECH2_T") (class "Default")
      (node (ref "J1") (pin "A40") (pinfunction "A40_A40") (pintype "bidirectional"))
      (node (ref "R42") (pin "2") (pinfunction "2_2") (pintype "passive"))
    )
    (net (code "18") (name "/CLK_REF") (class "Default")
      (node (ref "IC18") (pin "4") (pinfunction "CLK_4") (pintype "bidirectional"))
      (node (ref "IC19") (pin "4") (pinfunction "CLK_4") (pintype "bidirectional"))
      (node (ref "IC20") (pin "4") (pinfunction "CLK_4") (pintype "bidirectional"))
      (node (ref "J1") (pin "A8") (pinfunction "A8_A8") (pintype "bidirectional"))
    )
    (net (code "19") (name "/CLK_T") (class "Default")
      (node (ref "J1") (pin "A32") (pinfunction "A32_A32") (pintype "bidirectional"))
      (node (ref "R30") (pin "2") (pinfunction "2_2") (pintype "passive"))
    )
    (net (code "20") (name "/CS_B0") (class "Default")
      (node (ref "IC1") (pin "41") (pinfunction "CS_B0_41") (pintype "bidirectional"))
      (node (ref "R14") (pin "1") (pinfunction "1_1") (pintype "passive"))
      (node (ref "R15") (pin "2") (pinfunction "2_2") (pintype "passive"))
    )
    (net (code "21") (name "/CS_B0_T") (class "Default")
      (node (ref "J1") (pin "A26") (pinfunction "A26_A26") (pintype "bidirectional"))
      (node (ref "R14") (pin "2") (pinfunction "2_2") (pintype "passive"))
    )
    (net (code "22") (name "/CS_B1") (class "Default")
      (node (ref "IC1") (pin "42") (pinfunction "CS_B1_42") (pintype "bidirectional"))
      (node (ref "R16") (pin "1") (pinfunction "1_1") (pintype "passive"))
      (node (ref "R17") (pin "2") (pinfunction "2_2") (pintype "passive"))
    )
    (net (code "23") (name "/CS_B1_T") (class "Default")
      (node (ref "J1") (pin "A28") (pinfunction "A28_A28") (pintype "bidirectional"))
      (node (ref "R16") (pin "2") (pinfunction "2_2") (pintype "passive"))
    )
    (net (code "24") (name "/CS_B2") (class "Default")
      (node (ref "IC1") (pin "43") (pinfunction "CS_B2_43") (pintype "bidirectional"))
      (node (ref "R18") (pin "1") (pinfunction "1_1") (pintype "passive"))
      (node (ref "R19") (pin "2") (pinfunction "2_2") (pintype "passive"))
    )
    (net (code "25") (name "/CS_B2_T") (class "Default")
      (node (ref "J1") (pin "A30") (pinfunction "A30_A30") (pintype "bidirectional"))
      (node (ref "R18") (pin "2") (pinfunction "2_2") (pintype "passive"))
    )
    (net (code "26") (name "/CS_B3") (class "Default")
      (node (ref "IC1") (pin "44") (pinfunction "CS_B3_44") (pintype "bidirectional"))
      (node (ref "R20") (pin "1") (pinfunction "1_1") (pintype "passive"))
      (node (ref "R21") (pin "2") (pinfunction "2_2") (pintype "passive"))
    )
    (net (code "27") (name "/CS_B3_T") (class "Default")
      (node (ref "J1") (pin "A34") (pinfunction "A34_A34") (pintype "bidirectional"))
      (node (ref "R20") (pin "2") (pinfunction "2_2") (pintype "passive"))
    )
    (net (code "28") (name "/CS_B4") (class "Default")
      (node (ref "IC1") (pin "45") (pinfunction "CS_B4_45") (pintype "bidirectional"))
      (node (ref "R22") (pin "1") (pinfunction "1_1") (pintype "passive"))
      (node (ref "R23") (pin "2") (pinfunction "2_2") (pintype "passive"))
    )
    (net (code "29") (name "/CS_B4_T") (class "Default")
      (node (ref "J1") (pin "A36") (pinfunction "A36_A36") (pintype "bidirectional"))
      (node (ref "R22") (pin "2") (pinfunction "2_2") (pintype "passive"))
    )
    (net (code "30") (name "/CS_B5") (class "Default")
      (node (ref "IC1") (pin "46") (pinfunction "CS_B5_46") (pintype "bidirectional"))
      (node (ref "R24") (pin "1") (pinfunction "1_1") (pintype "passive"))
      (node (ref "R25") (pin "2") (pinfunction "2_2") (pintype "passive"))
    )
    (net (code "31") (name "/CS_B5_T") (class "Default")
      (node (ref "J1") (pin "A38") (pinfunction "A38_A38") (pintype "bidirectional"))
      (node (ref "R24") (pin "2") (pinfunction "2_2") (pintype "passive"))
    )
    (net (code "32") (name "/CS_REF_1") (class "Default")
      (node (ref "IC18") (pin "6") (pinfunction "CS~{}_6") (pintype "bidirectional"))
      (node (ref "J1") (pin "A12") (pinfunction "A12_A12") (pintype "bidirectional"))
    )
    (net (code "33") (name "/CS_REF_2") (class "Default")
      (node (ref "IC19") (pin "6") (pinfunction "CS~{}_6") (pintype "bidirectional"))
      (node (ref "J1") (pin "A10") (pinfunction "A10_A10") (pintype "bidirectional"))
    )
    (net (code "34") (name "/CS_REF_3") (class "Default")
      (node (ref "IC20") (pin "6") (pinfunction "CS~{}_6") (pintype "bidirectional"))
      (node (ref "J1") (pin "A7") (pinfunction "A7_A7") (pintype "bidirectional"))
    )
    (net (code "35") (name "/DGND") (class "Default")
      (node (ref "C11") (pin "2") (pinfunction "2_2") (pintype "passive"))
      (node (ref "C12") (pin "2") (pinfunction "2_2") (pintype "passive"))
      (node (ref "C13") (pin "2") (pinfunction "2_2") (pintype "passive"))
      (node (ref "C40") (pin "2") (pinfunction "2_2") (pintype "passive"))
      (node (ref "C5") (pin "2") (pinfunction "2_2") (pintype "passive"))
      (node (ref "IC1") (pin "28") (pinfunction "DGND_28") (pintype "power_in"))
      (node (ref "IC10") (pin "2") (pinfunction "GND_2") (pintype "bidirectional"))
      (node (ref "JP6") (pin "1") (pinfunction "1_1") (pintype "passive"))
      (node (ref "TP23") (pin "TP") (pinfunction "TP_TP") (pintype "input"))
      (node (ref "TP29") (pin "TP") (pinfunction "TP_TP") (pintype "input"))
    )
    (net (code "36") (name "/DVDD") (class "Default")
      (node (ref "C11") (pin "1") (pinfunction "1_1") (pintype "passive"))
      (node (ref "C12") (pin "1") (pinfunction "1_1") (pintype "passive"))
      (node (ref "C13") (pin "1") (pinfunction "1_1") (pintype "passive"))
      (node (ref "C40") (pin "1") (pinfunction "1_1") (pintype "passive"))
      (node (ref "IC1") (pin "27") (pinfunction "DVDD_27") (pintype "power_in"))
      (node (ref "IC10") (pin "5") (pinfunction "VREF_5") (pintype "bidirectional"))
      (node (ref "TP8") (pin "TP") (pinfunction "TP_TP") (pintype "input"))
    )
    (net (code "37") (name "/GND") (class "Default")
      (node (ref "C1") (pin "2") (pinfunction "2_2") (pintype "passive"))
      (node (ref "C14") (pin "2") (pinfunction "2_2") (pintype "passive"))
      (node (ref "C15") (pin "2") (pinfunction "2_2") (pintype "passive"))
      (node (ref "C16") (pin "2") (pinfunction "2_2") (pintype "passive"))
      (node (ref "C17") (pin "2") (pinfunction "2_2") (pintype "passive"))
      (node (ref "C18") (pin "2") (pinfunction "2_2") (pintype "passive"))
      (node (ref "C19") (pin "2") (pinfunction "2_2") (pintype "passive"))
      (node (ref "C2") (pin "2") (pinfunction "2_2") (pintype "passive"))
      (node (ref "C20") (pin "2") (pinfunction "2_2") (pintype "passive"))
      (node (ref "C21") (pin "2") (pinfunction "2_2") (pintype "passive"))
      (node (ref "C22") (pin "2") (pinfunction "2_2") (pintype "passive"))
      (node (ref "C23") (pin "2") (pinfunction "2_2") (pintype "passive"))
      (node (ref "C24") (pin "2") (pinfunction "2_2") (pintype "passive"))
      (node (ref "C25") (pin "2") (pinfunction "2_2") (pintype "passive"))
      (node (ref "C26") (pin "2") (pinfunction "2_2") (pintype "passive"))
      (node (ref "C27") (pin "2") (pinfunction "2_2") (pintype "passive"))
      (node (ref "C28") (pin "2") (pinfunction "2_2") (pintype "passive"))
      (node (ref "C29") (pin "2") (pinfunction "2_2") (pintype "passive"))
      (node (ref "C3") (pin "2") (pinfunction "2_2") (pintype "passive"))
      (node (ref "C30") (pin "2") (pinfunction "2_2") (pintype "passive"))
      (node (ref "C31") (pin "2") (pinfunction "2_2") (pintype "passive"))
      (node (ref "C32") (pin "2") (pinfunction "2_2") (pintype "passive"))
      (node (ref "C33") (pin "2") (pinfunction "2_2") (pintype "passive"))
      (node (ref "C34") (pin "2") (pinfunction "2_2") (pintype "passive"))
      (node (ref "C35") (pin "2") (pinfunction "2_2") (pintype "passive"))
      (node (ref "C39") (pin "1") (pinfunction "1_1") (pintype "passive"))
      (node (ref "C4") (pin "2") (pinfunction "2_2") (pintype "passive"))
      (node (ref "C42") (pin "2") (pinfunction "2_2") (pintype "passive"))
      (node (ref "C43") (pin "2") (pinfunction "2_2") (pintype "passive"))
      (node (ref "C44") (pin "2") (pinfunction "2_2") (pintype "passive"))
      (node (ref "C45") (pin "2") (pinfunction "2_2") (pintype "passive"))
      (node (ref "C46") (pin "2") (pinfunction "2_2") (pintype "passive"))
      (node (ref "C47") (pin "2") (pinfunction "2_2") (pintype "passive"))
      (node (ref "C48") (pin "2") (pinfunction "2_2") (pintype "passive"))
      (node (ref "C49") (pin "2") (pinfunction "2_2") (pintype "passive"))
      (node (ref "C50") (pin "2") (pinfunction "2_2") (pintype "passive"))
      (node (ref "C51") (pin "2") (pinfunction "2_2") (pintype "passive"))
      (node (ref "C52") (pin "2") (pinfunction "2_2") (pintype "passive"))
      (node (ref "C53") (pin "2") (pinfunction "2_2") (pintype "passive"))
      (node (ref "C54") (pin "2") (pinfunction "2_2") (pintype "passive"))
      (node (ref "C55") (pin "2") (pinfunction "2_2") (pintype "passive"))
      (node (ref "C56") (pin "2") (pinfunction "2_2") (pintype "passive"))
      (node (ref "C57") (pin "2") (pinfunction "2_2") (pintype "passive"))
      (node (ref "C8") (pin "2") (pinfunction "2_2") (pintype "passive"))
      (node (ref "IC11") (pin "2") (pinfunction "GND_2") (pintype "passive"))
      (node (ref "IC15") (pin "2") (pinfunction "GND_2") (pintype "passive"))
      (node (ref "IC16") (pin "2") (pinfunction "GND_2") (pintype "bidirectional"))
      (node (ref "IC17") (pin "2") (pinfunction "GND_2") (pintype "bidirectional"))
      (node (ref "IC18") (pin "3") (pinfunction "GND_3") (pintype "bidirectional"))
      (node (ref "IC18") (pin "8") (pinfunction "A_8") (pintype "bidirectional"))
      (node (ref "IC19") (pin "3") (pinfunction "GND_3") (pintype "bidirectional"))
      (node (ref "IC19") (pin "8") (pinfunction "A_8") (pintype "bidirectional"))
      (node (ref "IC2") (pin "2") (pinfunction "GND_2") (pintype "bidirectional"))
      (node (ref "IC20") (pin "3") (pinfunction "GND_3") (pintype "bidirectional"))
      (node (ref "IC20") (pin "8") (pinfunction "A_8") (pintype "bidirectional"))
      (node (ref "IC21") (pin "10") (pinfunction "S3B_10") (pintype "bidirectional"))
      (node (ref "IC21") (pin "13") (pinfunction "S4B_13") (pintype "bidirectional"))
      (node (ref "IC21") (pin "8") (pinfunction "GND_8") (pintype "bidirectional"))
      (node (ref "IC22") (pin "P$3") (pinfunction "RGND_P$3") (pintype "bidirectional"))
      (node (ref "IC22") (pin "P$6") (pinfunction "GND_P$6") (pintype "bidirectional"))
      (node (ref "IC23") (pin "3") (pinfunction "GND_3") (pintype "bidirectional"))
      (node (ref "IC3") (pin "2") (pinfunction "GND_2") (pintype "bidirectional"))
      (node (ref "IC4") (pin "2") (pinfunction "GND_2") (pintype "bidirectional"))
      (node (ref "IC5") (pin "2") (pinfunction "GND_2") (pintype "bidirectional"))
      (node (ref "IC6") (pin "2") (pinfunction "GND_2") (pintype "bidirectional"))
      (node (ref "IC7") (pin "2") (pinfunction "GND_2") (pintype "bidirectional"))
      (node (ref "IC8") (pin "2") (pinfunction "GND_2") (pintype "bidirectional"))
      (node (ref "IC9") (pin "2") (pinfunction "GND_2") (pintype "passive"))
      (node (ref "J1") (pin "B10") (pinfunction "B10_B10") (pintype "bidirectional"))
      (node (ref "J1") (pin "B11") (pinfunction "B11_B11") (pintype "bidirectional"))
      (node (ref "J1") (pin "B12") (pinfunction "B12_B12") (pintype "bidirectional"))
      (node (ref "J1") (pin "B13") (pinfunction "B13_B13") (pintype "bidirectional"))
      (node (ref "J1") (pin "B14") (pinfunction "B14_B14") (pintype "bidirectional"))
      (node (ref "J1") (pin "B15") (pinfunction "B15_B15") (pintype "bidirectional"))
      (node (ref "J1") (pin "B16") (pinfunction "B16_B16") (pintype "bidirectional"))
      (node (ref "J1") (pin "B17") (pinfunction "B17_B17") (pintype "bidirectional"))
      (node (ref "J1") (pin "B18") (pinfunction "B18_B18") (pintype "bidirectional"))
      (node (ref "J1") (pin "B19") (pinfunction "B19_B19") (pintype "bidirectional"))
      (node (ref "J1") (pin "B2") (pinfunction "B2_B2") (pintype "bidirectional"))
      (node (ref "J1") (pin "B20") (pinfunction "B20_B20") (pintype "bidirectional"))
      (node (ref "J1") (pin "B21") (pinfunction "B21_B21") (pintype "bidirectional"))
      (node (ref "J1") (pin "B22") (pinfunction "B22_B22") (pintype "bidirectional"))
      (node (ref "J1") (pin "B23") (pinfunction "B23_B23") (pintype "bidirectional"))
      (node (ref "J1") (pin "B24") (pinfunction "B24_B24") (pintype "bidirectional"))
      (node (ref "J1") (pin "B25") (pinfunction "B25_B25") (pintype "bidirectional"))
      (node (ref "J1") (pin "B26") (pinfunction "B26_B26") (pintype "bidirectional"))
      (node (ref "J1") (pin "B27") (pinfunction "B27_B27") (pintype "bidirectional"))
      (node (ref "J1") (pin "B28") (pinfunction "B28_B28") (pintype "bidirectional"))
      (node (ref "J1") (pin "B29") (pinfunction "B29_B29") (pintype "bidirectional"))
      (node (ref "J1") (pin "B30") (pinfunction "B30_B30") (pintype "bidirectional"))
      (node (ref "J1") (pin "B31") (pinfunction "B31_B31") (pintype "bidirectional"))
      (node (ref "J1") (pin "B32") (pinfunction "B32_B32") (pintype "bidirectional"))
      (node (ref "J1") (pin "B33") (pinfunction "B33_B33") (pintype "bidirectional"))
      (node (ref "J1") (pin "B34") (pinfunction "B34_B34") (pintype "bidirectional"))
      (node (ref "J1") (pin "B35") (pinfunction "B35_B35") (pintype "bidirectional"))
      (node (ref "J1") (pin "B36") (pinfunction "B36_B36") (pintype "bidirectional"))
      (node (ref "J1") (pin "B37") (pinfunction "B37_B37") (pintype "bidirectional"))
      (node (ref "J1") (pin "B38") (pinfunction "B38_B38") (pintype "bidirectional"))
      (node (ref "J1") (pin "B39") (pinfunction "B39_B39") (pintype "bidirectional"))
      (node (ref "J1") (pin "B40") (pinfunction "B40_B40") (pintype "bidirectional"))
      (node (ref "J1") (pin "B41") (pinfunction "B41_B41") (pintype "bidirectional"))
      (node (ref "J1") (pin "B42") (pinfunction "B42_B42") (pintype "bidirectional"))
      (node (ref "J1") (pin "B43") (pinfunction "B43_B43") (pintype "bidirectional"))
      (node (ref "J1") (pin "B44") (pinfunction "B44_B44") (pintype "bidirectional"))
      (node (ref "J1") (pin "B45") (pinfunction "B45_B45") (pintype "bidirectional"))
      (node (ref "J1") (pin "B47") (pinfunction "B47_B47") (pintype "bidirectional"))
      (node (ref "J1") (pin "B5") (pinfunction "B5_B5") (pintype "bidirectional"))
      (node (ref "J1") (pin "B6") (pinfunction "B6_B6") (pintype "bidirectional"))
      (node (ref "J1") (pin "B7") (pinfunction "B7_B7") (pintype "bidirectional"))
      (node (ref "J1") (pin "B8") (pinfunction "B8_B8") (pintype "bidirectional"))
      (node (ref "J1") (pin "B9") (pinfunction "B9_B9") (pintype "bidirectional"))
      (node (ref "JP14") (pin "1") (pinfunction "1_1") (pintype "passive"))
      (node (ref "JP17") (pin "3") (pinfunction "P$3_3") (pintype "bidirectional"))
      (node (ref "JP2") (pin "1") (pinfunction "1_1") (pintype "passive"))
      (node (ref "R15") (pin "1") (pinfunction "1_1") (pintype "passive"))
      (node (ref "R17") (pin "1") (pinfunction "1_1") (pintype "passive"))
      (node (ref "R19") (pin "1") (pinfunction "1_1") (pintype "passive"))
      (node (ref "R21") (pin "1") (pinfunction "1_1") (pintype "passive"))
      (node (ref "R23") (pin "1") (pinfunction "1_1") (pintype "passive"))
      (node (ref "R25") (pin "1") (pinfunction "1_1") (pintype "passive"))
      (node (ref "R27") (pin "1") (pinfunction "1_1") (pintype "passive"))
      (node (ref "R29") (pin "1") (pinfunction "1_1") (pintype "passive"))
      (node (ref "R31") (pin "1") (pinfunction "1_1") (pintype "passive"))
      (node (ref "R33") (pin "1") (pinfunction "1_1") (pintype "passive"))
      (node (ref "R35") (pin "1") (pinfunction "1_1") (pintype "passive"))
      (node (ref "R37") (pin "1") (pinfunction "1_1") (pintype "passive"))
      (node (ref "R39") (pin "1") (pinfunction "1_1") (pintype "passive"))
      (node (ref "R4") (pin "3") (pinfunction "3_3") (pintype "passive"))
      (node (ref "R41") (pin "1") (pinfunction "1_1") (pintype "passive"))
      (node (ref "R43") (pin "1") (pinfunction "1_1") (pintype "passive"))
      (node (ref "R5") (pin "3") (pinfunction "3_3") (pintype "passive"))
      (node (ref "R6") (pin "3") (pinfunction "3_3") (pintype "passive"))
      (node (ref "R8") (pin "1") (pinfunction "1_1") (pintype "passive"))
      (node (ref "R9") (pin "1") (pinfunction "1_1") (pintype "passive"))
      (node (ref "TP18") (pin "TP") (pinfunction "TP_TP") (pintype "input"))
      (node (ref "TP31") (pin "TP") (pinfunction "TP_TP") (pintype "input"))
      (node (ref "TP32") (pin "TP") (pinfunction "TP_TP") (pintype "input"))
      (node (ref "TP33") (pin "TP") (pinfunction "TP_TP") (pintype "input"))
      (node (ref "TP34") (pin "TP") (pinfunction "TP_TP") (pintype "input"))
      (node (ref "TP35") (pin "TP") (pinfunction "TP_TP") (pintype "input"))
      (node (ref "TP36") (pin "TP") (pinfunction "TP_TP") (pintype "input"))
      (node (ref "TP38") (pin "TP") (pinfunction "TP_TP") (pintype "input"))
      (node (ref "U$5") (pin "P$3") (pinfunction "RGND_P$3") (pintype "bidirectional"))
      (node (ref "U$5") (pin "P$6") (pinfunction "GND_P$6") (pintype "bidirectional"))
    )
    (net (code "38") (name "/HOLD") (class "Default")
      (node (ref "IC1") (pin "37") (pinfunction "HOLD_37") (pintype "bidirectional"))
      (node (ref "R38") (pin "1") (pinfunction "1_1") (pintype "passive"))
      (node (ref "R39") (pin "2") (pinfunction "2_2") (pintype "passive"))
    )
    (net (code "39") (name "/HOLD_T") (class "Default")
      (node (ref "J1") (pin "A23") (pinfunction "A23_A23") (pintype "bidirectional"))
      (node (ref "R38") (pin "2") (pinfunction "2_2") (pintype "passive"))
    )
    (net (code "40") (name "/MUX_DAC_EN") (class "Default")
      (node (ref "IC21") (pin "15") (pinfunction "~{EN}_15") (pintype "bidirectional"))
      (node (ref "J1") (pin "A21") (pinfunction "A21_A21") (pintype "bidirectional"))
    )
    (net (code "41") (name "/MUX_DAC_SEL") (class "Default")
      (node (ref "IC21") (pin "1") (pinfunction "IN_1") (pintype "bidirectional"))
      (node (ref "J1") (pin "A20") (pinfunction "A20_A20") (pintype "bidirectional"))
    )
    (net (code "42") (name "/MUX_REF_1") (class "Default")
      (node (ref "IC2") (pin "6") (pinfunction "IN_6") (pintype "bidirectional"))
      (node (ref "J1") (pin "A13") (pinfunction "A13_A13") (pintype "bidirectional"))
    )
    (net (code "43") (name "/MUX_REF_2") (class "Default")
      (node (ref "IC3") (pin "6") (pinfunction "IN_6") (pintype "bidirectional"))
      (node (ref "J1") (pin "A11") (pinfunction "A11_A11") (pintype "bidirectional"))
    )
    (net (code "44") (name "/MUX_REF_3") (class "Default")
      (node (ref "IC4") (pin "6") (pinfunction "IN_6") (pintype "bidirectional"))
      (node (ref "J1") (pin "A9") (pinfunction "A9_A9") (pintype "bidirectional"))
    )
    (net (code "45") (name "/N$9") (class "Default")
      (node (ref "JP13") (pin "1") (pinfunction "1_1") (pintype "passive"))
      (node (ref "JP19") (pin "2") (pinfunction "2_2") (pintype "passive"))
    )
    (net (code "46") (name "/OP_MODE") (class "Default")
      (node (ref "IC1") (pin "11") (pinfunction "OP_MODE_11") (pintype "bidirectional"))
      (node (ref "R26") (pin "1") (pinfunction "1_1") (pintype "passive"))
      (node (ref "R27") (pin "2") (pinfunction "2_2") (pintype "passive"))
    )
    (net (code "47") (name "/OP_MODE_T") (class "Default")
      (node (ref "J1") (pin "A35") (pinfunction "A35_A35") (pintype "bidirectional"))
      (node (ref "R26") (pin "2") (pinfunction "2_2") (pintype "passive"))
    )
    (net (code "48") (name "/OUT_S") (class "Default")
      (node (ref "IC1") (pin "35") (pinfunction "OUT_S_35") (pintype "bidirectional"))
      (node (ref "R32") (pin "1") (pinfunction "1_1") (pintype "passive"))
      (node (ref "R33") (pin "2") (pinfunction "2_2") (pintype "passive"))
    )
    (net (code "49") (name "/OUT_S_T") (class "Default")
      (node (ref "J1") (pin "A22") (pinfunction "A22_A22") (pintype "bidirectional"))
      (node (ref "R32") (pin "2") (pinfunction "2_2") (pintype "passive"))
    )
    (net (code "50") (name "/POT_R1") (class "Default")
      (node (ref "JP4") (pin "3") (pinfunction "3_3") (pintype "passive"))
      (node (ref "R1") (pin "2") (pinfunction "2_2") (pintype "passive"))
      (node (ref "R1") (pin "3") (pinfunction "3_3") (pintype "passive"))
      (node (ref "TP27") (pin "TP") (pinfunction "TP_TP") (pintype "input"))
    )
    (net (code "51") (name "/POT_R2") (class "Default")
      (node (ref "JP4") (pin "1") (pinfunction "1_1") (pintype "passive"))
      (node (ref "R2") (pin "1") (pinfunction "1_1") (pintype "passive"))
      (node (ref "R2") (pin "2") (pinfunction "2_2") (pintype "passive"))
      (node (ref "TP28") (pin "TP") (pinfunction "TP_TP") (pintype "input"))
    )
    (net (code "52") (name "/POT_R4") (class "Default")
      (node (ref "IC2") (pin "3") (pinfunction "A1_3") (pintype "bidirectional"))
      (node (ref "R4") (pin "2") (pinfunction "2_2") (pintype "passive"))
      (node (ref "TP24") (pin "TP") (pinfunction "TP_TP") (pintype "input"))
    )
    (net (code "53") (name "/POT_R5") (class "Default")
      (node (ref "IC3") (pin "3") (pinfunction "A1_3") (pintype "bidirectional"))
      (node (ref "R5") (pin "2") (pinfunction "2_2") (pintype "passive"))
      (node (ref "TP25") (pin "TP") (pinfunction "TP_TP") (pintype "input"))
    )
    (net (code "54") (name "/POT_R6") (class "Default")
      (node (ref "IC4") (pin "3") (pinfunction "A1_3") (pintype "bidirectional"))
      (node (ref "R6") (pin "2") (pinfunction "2_2") (pintype "passive"))
      (node (ref "TP26") (pin "TP") (pinfunction "TP_TP") (pintype "input"))
    )
    (net (code "55") (name "/REFIN_DAC") (class "Default")
      (node (ref "C28") (pin "1") (pinfunction "1_1") (pintype "passive"))
      (node (ref "IC23") (pin "10") (pinfunction "REFIN_10") (pintype "bidirectional"))
      (node (ref "IC8") (pin "5") (pinfunction "VREF_5") (pintype "bidirectional"))
      (node (ref "TP15") (pin "TP") (pinfunction "TP_TP") (pintype "input"))
    )
    (net (code "56") (name "/REF_ADC") (class "Default")
      (node (ref "C17") (pin "1") (pinfunction "1_1") (pintype "passive"))
      (node (ref "C18") (pin "1") (pinfunction "1_1") (pintype "passive"))
      (node (ref "C23") (pin "1") (pinfunction "1_1") (pintype "passive"))
      (node (ref "C24") (pin "1") (pinfunction "1_1") (pintype "passive"))
      (node (ref "C31") (pin "1") (pinfunction "1_1") (pintype "passive"))
      (node (ref "IC17") (pin "5") (pinfunction "VREF_5") (pintype "bidirectional"))
      (node (ref "IC22") (pin "P$2") (pinfunction "REF_P$2") (pintype "bidirectional"))
      (node (ref "TP17") (pin "TP") (pinfunction "TP_TP") (pintype "input"))
      (node (ref "U$5") (pin "P$2") (pinfunction "REF_P$2") (pintype "bidirectional"))
    )
    (net (code "57") (name "/RES_BIAS_EXT") (class "Default")
      (node (ref "IC1") (pin "6") (pinfunction "RES_BIAS_EXT_6") (pintype "bidirectional"))
      (node (ref "JP4") (pin "2") (pinfunction "2_2") (pintype "passive"))
    )
    (net (code "58") (name "/RST") (class "Default")
      (node (ref "IC1") (pin "38") (pinfunction "RST_38") (pintype "bidirectional"))
      (node (ref "R36") (pin "1") (pinfunction "1_1") (pintype "passive"))
      (node (ref "R37") (pin "2") (pinfunction "2_2") (pintype "passive"))
    )
    (net (code "59") (name "/RST_CSA") (class "Default")
      (node (ref "IC1") (pin "12") (pinfunction "RST_CSA_12") (pintype "bidirectional"))
      (node (ref "R28") (pin "1") (pinfunction "1_1") (pintype "passive"))
      (node (ref "R29") (pin "2") (pinfunction "2_2") (pintype "passive"))
    )
    (net (code "60") (name "/RST_CSA_T") (class "Default")
      (node (ref "J1") (pin "A33") (pinfunction "A33_A33") (pintype "bidirectional"))
      (node (ref "R28") (pin "2") (pinfunction "2_2") (pintype "passive"))
    )
    (net (code "61") (name "/RST_T") (class "Default")
      (node (ref "J1") (pin "A24") (pinfunction "A24_A24") (pintype "bidirectional"))
      (node (ref "R36") (pin "2") (pinfunction "2_2") (pintype "passive"))
    )
    (net (code "62") (name "/SDI_DAC") (class "Default")
      (node (ref "IC23") (pin "7") (pinfunction "DIN_7") (pintype "bidirectional"))
      (node (ref "J1") (pin "A18") (pinfunction "A18_A18") (pintype "bidirectional"))
    )
    (net (code "63") (name "/SDI_REF") (class "Default")
      (node (ref "IC18") (pin "5") (pinfunction "SDI_5") (pintype "bidirectional"))
      (node (ref "IC19") (pin "5") (pinfunction "SDI_5") (pintype "bidirectional"))
      (node (ref "IC20") (pin "5") (pinfunction "SDI_5") (pintype "bidirectional"))
      (node (ref "J1") (pin "A6") (pinfunction "A6_A6") (pintype "bidirectional"))
    )
    (net (code "64") (name "/SDO_ADC1") (class "Default")
      (node (ref "IC22") (pin "P$8") (pinfunction "DOUT_P$8") (pintype "bidirectional"))
      (node (ref "J1") (pin "A43") (pinfunction "A43_A43") (pintype "bidirectional"))
      (node (ref "R3") (pin "1") (pinfunction "1_1") (pintype "passive"))
    )
    (net (code "65") (name "/SDO_ADC2") (class "Default")
      (node (ref "J1") (pin "A14") (pinfunction "A14_A14") (pintype "bidirectional"))
      (node (ref "R7") (pin "1") (pinfunction "1_1") (pintype "passive"))
      (node (ref "U$5") (pin "P$8") (pinfunction "DOUT_P$8") (pintype "bidirectional"))
    )
    (net (code "66") (name "/SGN") (class "Default")
      (node (ref "IC1") (pin "39") (pinfunction "SGN_39") (pintype "bidirectional"))
      (node (ref "R34") (pin "1") (pinfunction "1_1") (pintype "passive"))
      (node (ref "R35") (pin "2") (pinfunction "2_2") (pintype "passive"))
    )
    (net (code "67") (name "/SGN_T") (class "Default")
      (node (ref "J1") (pin "A25") (pinfunction "A25_A25") (pintype "bidirectional"))
      (node (ref "R34") (pin "2") (pinfunction "2_2") (pintype "passive"))
    )
    (net (code "68") (name "/V0NDAC") (class "Default")
      (node (ref "IC21") (pin "5") (pinfunction "S2A_5") (pintype "bidirectional"))
      (node (ref "IC23") (pin "2") (pinfunction "VOUTB_2") (pintype "bidirectional"))
    )
    (net (code "69") (name "/V0PDAC") (class "Default")
      (node (ref "IC21") (pin "2") (pinfunction "S1A_2") (pintype "bidirectional"))
      (node (ref "IC23") (pin "1") (pinfunction "VOUTA_1") (pintype "bidirectional"))
    )
    (net (code "70") (name "/V1NDAC") (class "Default")
      (node (ref "C53") (pin "1") (pinfunction "1_1") (pintype "passive"))
      (node (ref "IC21") (pin "14") (pinfunction "S4A_14") (pintype "bidirectional"))
      (node (ref "IC23") (pin "5") (pinfunction "VOUTD_5") (pintype "bidirectional"))
    )
    (net (code "71") (name "/V1PDAC") (class "Default")
      (node (ref "C52") (pin "1") (pinfunction "1_1") (pintype "passive"))
      (node (ref "IC21") (pin "11") (pinfunction "S3A_11") (pintype "bidirectional"))
      (node (ref "IC23") (pin "4") (pinfunction "VOUTC_4") (pintype "bidirectional"))
    )
    (net (code "72") (name "/VDD") (class "Default")
      (node (ref "C1") (pin "1") (pinfunction "1_1") (pintype "passive"))
      (node (ref "C2") (pin "1") (pinfunction "1_1") (pintype "passive"))
      (node (ref "C3") (pin "1") (pinfunction "1_1") (pintype "passive"))
      (node (ref "C39") (pin "2") (pinfunction "2_2") (pintype "passive"))
      (node (ref "C44") (pin "1") (pinfunction "1_1") (pintype "passive"))
      (node (ref "IC11") (pin "3") (pinfunction "VO_3") (pintype "passive"))
      (node (ref "IC18") (pin "2") (pinfunction "VDD_2") (pintype "bidirectional"))
      (node (ref "IC19") (pin "2") (pinfunction "VDD_2") (pintype "bidirectional"))
      (node (ref "IC2") (pin "5") (pinfunction "VCC_5") (pintype "bidirectional"))
      (node (ref "IC20") (pin "2") (pinfunction "VDD_2") (pintype "bidirectional"))
      (node (ref "IC21") (pin "16") (pinfunction "VDD_16") (pintype "bidirectional"))
      (node (ref "IC23") (pin "8") (pinfunction "VDD_8") (pintype "bidirectional"))
      (node (ref "IC3") (pin "5") (pinfunction "VCC_5") (pintype "bidirectional"))
      (node (ref "IC4") (pin "5") (pinfunction "VCC_5") (pintype "bidirectional"))
      (node (ref "IC5") (pin "3") (pinfunction "EN_3") (pintype "bidirectional"))
      (node (ref "IC5") (pin "4") (pinfunction "VIN_4") (pintype "bidirectional"))
      (node (ref "IC6") (pin "3") (pinfunction "EN_3") (pintype "bidirectional"))
      (node (ref "IC6") (pin "4") (pinfunction "VIN_4") (pintype "bidirectional"))
      (node (ref "IC7") (pin "3") (pinfunction "EN_3") (pintype "bidirectional"))
      (node (ref "IC7") (pin "4") (pinfunction "VIN_4") (pintype "bidirectional"))
      (node (ref "TP5") (pin "TP") (pinfunction "TP_TP") (pintype "input"))
    )
    (net (code "73") (name "/VDD2") (class "Default")
      (node (ref "C46") (pin "1") (pinfunction "1_1") (pintype "passive"))
      (node (ref "C5") (pin "1") (pinfunction "1_1") (pintype "passive"))
      (node (ref "C7") (pin "1") (pinfunction "1_1") (pintype "passive"))
      (node (ref "IC10") (pin "3") (pinfunction "EN_3") (pintype "bidirectional"))
      (node (ref "IC10") (pin "4") (pinfunction "VIN_4") (pintype "bidirectional"))
      (node (ref "IC13") (pin "3") (pinfunction "EN_3") (pintype "bidirectional"))
      (node (ref "IC13") (pin "4") (pinfunction "VIN_4") (pintype "bidirectional"))
      (node (ref "IC9") (pin "3") (pinfunction "VO_3") (pintype "passive"))
      (node (ref "TP6") (pin "TP") (pinfunction "TP_TP") (pintype "input"))
    )
    (net (code "74") (name "/VDD3") (class "Default")
      (node (ref "C15") (pin "1") (pinfunction "1_1") (pintype "passive"))
      (node (ref "C16") (pin "1") (pinfunction "1_1") (pintype "passive"))
      (node (ref "C19") (pin "1") (pinfunction "1_1") (pintype "passive"))
      (node (ref "C20") (pin "1") (pinfunction "1_1") (pintype "passive"))
      (node (ref "C25") (pin "1") (pinfunction "1_1") (pintype "passive"))
      (node (ref "C30") (pin "1") (pinfunction "1_1") (pintype "passive"))
      (node (ref "C4") (pin "1") (pinfunction "1_1") (pintype "passive"))
      (node (ref "C51") (pin "1") (pinfunction "1_1") (pintype "passive"))
      (node (ref "IC12") (pin "8") (pinfunction "V+_8") (pintype "bidirectional"))
      (node (ref "IC14") (pin "8") (pinfunction "V+_8") (pintype "bidirectional"))
      (node (ref "IC15") (pin "3") (pinfunction "VO_3") (pintype "passive"))
      (node (ref "IC16") (pin "3") (pinfunction "EN_3") (pintype "bidirectional"))
      (node (ref "IC16") (pin "4") (pinfunction "VIN_4") (pintype "bidirectional"))
      (node (ref "IC17") (pin "3") (pinfunction "EN_3") (pintype "bidirectional"))
      (node (ref "IC17") (pin "4") (pinfunction "VIN_4") (pintype "bidirectional"))
      (node (ref "IC22") (pin "P$4") (pinfunction "VDD_P$4") (pintype "bidirectional"))
      (node (ref "IC8") (pin "3") (pinfunction "EN_3") (pintype "bidirectional"))
      (node (ref "IC8") (pin "4") (pinfunction "VIN_4") (pintype "bidirectional"))
      (node (ref "TP45") (pin "TP") (pinfunction "TP_TP") (pintype "input"))
      (node (ref "U$5") (pin "P$4") (pinfunction "VDD_P$4") (pintype "bidirectional"))
    )
    (net (code "75") (name "/VDD_REF_1") (class "Default")
      (node (ref "C26") (pin "1") (pinfunction "1_1") (pintype "passive"))
      (node (ref "IC18") (pin "7") (pinfunction "B_7") (pintype "bidirectional"))
      (node (ref "IC5") (pin "5") (pinfunction "VREF_5") (pintype "bidirectional"))
      (node (ref "R4") (pin "1") (pinfunction "1_1") (pintype "passive"))
      (node (ref "TP41") (pin "TP") (pinfunction "TP_TP") (pintype "input"))
    )
    (net (code "76") (name "/VDD_REF_2") (class "Default")
      (node (ref "C27") (pin "1") (pinfunction "1_1") (pintype "passive"))
      (node (ref "IC19") (pin "7") (pinfunction "B_7") (pintype "bidirectional"))
      (node (ref "IC6") (pin "5") (pinfunction "VREF_5") (pintype "bidirectional"))
      (node (ref "R5") (pin "1") (pinfunction "1_1") (pintype "passive"))
      (node (ref "TP42") (pin "TP") (pinfunction "TP_TP") (pintype "input"))
    )
    (net (code "77") (name "/VDD_REF_3") (class "Default")
      (node (ref "C35") (pin "1") (pinfunction "1_1") (pintype "passive"))
      (node (ref "IC20") (pin "7") (pinfunction "B_7") (pintype "bidirectional"))
      (node (ref "IC7") (pin "5") (pinfunction "VREF_5") (pintype "bidirectional"))
      (node (ref "R6") (pin "1") (pinfunction "1_1") (pintype "passive"))
      (node (ref "TP43") (pin "TP") (pinfunction "TP_TP") (pintype "input"))
    )
    (net (code "78") (name "/VDD_SUPPLY_1") (class "Default")
      (node (ref "C43") (pin "1") (pinfunction "1_1") (pintype "passive"))
      (node (ref "IC11") (pin "1") (pinfunction "VI_1") (pintype "input"))
      (node (ref "JP5") (pin "1") (pinfunction "1_1") (pintype "passive"))
      (node (ref "TP1") (pin "TP") (pinfunction "TP_TP") (pintype "input"))
    )
    (net (code "79") (name "/VDD_SUPPLY_2") (class "Default")
      (node (ref "C45") (pin "1") (pinfunction "1_1") (pintype "passive"))
      (node (ref "IC9") (pin "1") (pinfunction "VI_1") (pintype "input"))
      (node (ref "JP8") (pin "1") (pinfunction "1_1") (pintype "passive"))
      (node (ref "TP3") (pin "TP") (pinfunction "TP_TP") (pintype "input"))
    )
    (net (code "80") (name "/VDD_SUPPLY_3") (class "Default")
      (node (ref "C50") (pin "1") (pinfunction "1_1") (pintype "passive"))
      (node (ref "IC15") (pin "1") (pinfunction "VI_1") (pintype "input"))
      (node (ref "JP20") (pin "1") (pinfunction "1_1") (pintype "passive"))
      (node (ref "TP44") (pin "TP") (pinfunction "TP_TP") (pintype "input"))
    )
    (net (code "81") (name "/VDD_SUPPLY_IN_1") (class "Default")
      (node (ref "JP17") (pin "1") (pinfunction "P$1_1") (pintype "bidirectional"))
      (node (ref "JP20") (pin "2") (pinfunction "2_2") (pintype "passive"))
      (node (ref "JP5") (pin "2") (pinfunction "2_2") (pintype "passive"))
      (node (ref "TP2") (pin "TP") (pinfunction "TP_TP") (pintype "input"))
    )
    (net (code "82") (name "/VDD_SUPPLY_IN_2") (class "Default")
      (node (ref "JP17") (pin "2") (pinfunction "P$2_2") (pintype "bidirectional"))
      (node (ref "JP8") (pin "2") (pinfunction "2_2") (pintype "passive"))
      (node (ref "TP4") (pin "TP") (pinfunction "TP_TP") (pintype "input"))
    )
    (net (code "83") (name "/VI+_FIL") (class "Default")
      (node (ref "IC1") (pin "22") (pinfunction "VI+_FIL_22") (pintype "input"))
      (node (ref "JP11") (pin "2") (pinfunction "2_2") (pintype "passive"))
    )
    (net (code "84") (name "/VI+_FIL_DAC") (class "Default")
      (node (ref "C54") (pin "1") (pinfunction "1_1") (pintype "passive"))
      (node (ref "IC21") (pin "4") (pinfunction "D1_4") (pintype "bidirectional"))
      (node (ref "JP11") (pin "1") (pinfunction "1_1") (pintype "passive"))
    )
    (net (code "85") (name "/VI-_FIL") (class "Default")
      (node (ref "IC1") (pin "23") (pinfunction "VI-_FIL_23") (pintype "input"))
      (node (ref "JP12") (pin "2") (pinfunction "2_2") (pintype "passive"))
    )
    (net (code "86") (name "/VI-_FIL_DAC") (class "Default")
      (node (ref "C55") (pin "1") (pinfunction "1_1") (pintype "passive"))
      (node (ref "IC21") (pin "7") (pinfunction "D2_7") (pintype "bidirectional"))
      (node (ref "JP12") (pin "1") (pinfunction "1_1") (pintype "passive"))
    )
    (net (code "87") (name "/VICM") (class "Default")
      (node (ref "IC1") (pin "40") (pinfunction "VICM_40") (pintype "input"))
      (node (ref "IC21") (pin "3") (pinfunction "S1B_3") (pintype "bidirectional"))
      (node (ref "IC21") (pin "6") (pinfunction "S2B_6") (pintype "bidirectional"))
      (node (ref "JP15") (pin "2") (pinfunction "2_2") (pintype "passive"))
      (node (ref "TP12") (pin "TP") (pinfunction "TP_TP") (pintype "input"))
    )
    (net (code "88") (name "/VICM_BUFF") (class "Default")
      (node (ref "C32") (pin "1") (pinfunction "1_1") (pintype "passive"))
      (node (ref "IC12") (pin "1") (pinfunction "OUTA_1") (pintype "bidirectional"))
      (node (ref "IC12") (pin "2") (pinfunction "-INA_2") (pintype "bidirectional"))
      (node (ref "JP15") (pin "1") (pinfunction "1_1") (pintype "passive"))
    )
    (net (code "89") (name "/VICM_MUX") (class "Default")
      (node (ref "C47") (pin "1") (pinfunction "1_1") (pintype "passive"))
      (node (ref "IC12") (pin "3") (pinfunction "+INA_3") (pintype "bidirectional"))
      (node (ref "IC3") (pin "4") (pinfunction "B_4") (pintype "bidirectional"))
      (node (ref "JP15") (pin "3") (pinfunction "3_3") (pintype "passive"))
      (node (ref "TP11") (pin "TP") (pinfunction "TP_TP") (pintype "input"))
    )
    (net (code "90") (name "/VIN_CSA") (class "Default")
      (node (ref "IC1") (pin "15") (pinfunction "VIN_CSA_15") (pintype "input"))
      (node (ref "JP1") (pin "3") (pinfunction "3_3") (pintype "passive"))
      (node (ref "JP10") (pin "2") (pinfunction "2_2") (pintype "passive"))
      (node (ref "TP20") (pin "TP") (pinfunction "TP_TP") (pintype "input"))
    )
    (net (code "91") (name "/VIN_CSA_1") (class "Default")
      (node (ref "C36") (pin "1") (pinfunction "1_1") (pintype "passive"))
      (node (ref "C56") (pin "1") (pinfunction "1_1") (pintype "passive"))
      (node (ref "IC21") (pin "9") (pinfunction "D3_9") (pintype "bidirectional"))
      (node (ref "JP9") (pin "1") (pinfunction "1_1") (pintype "passive"))
    )
    (net (code "92") (name "/VL_ADC") (class "Default")
      (node (ref "C14") (pin "1") (pinfunction "1_1") (pintype "passive"))
      (node (ref "C21") (pin "1") (pinfunction "1_1") (pintype "passive"))
      (node (ref "C22") (pin "1") (pinfunction "1_1") (pintype "passive"))
      (node (ref "C29") (pin "1") (pinfunction "1_1") (pintype "passive"))
      (node (ref "C8") (pin "1") (pinfunction "1_1") (pintype "passive"))
      (node (ref "IC16") (pin "5") (pinfunction "VREF_5") (pintype "bidirectional"))
      (node (ref "IC22") (pin "P$7") (pinfunction "VL_P$7") (pintype "bidirectional"))
      (node (ref "R3") (pin "2") (pinfunction "2_2") (pintype "passive"))
      (node (ref "R7") (pin "2") (pinfunction "2_2") (pintype "passive"))
      (node (ref "TP16") (pin "TP") (pinfunction "TP_TP") (pintype "input"))
      (node (ref "U$5") (pin "P$7") (pinfunction "VL_P$7") (pintype "bidirectional"))
    )
    (net (code "93") (name "/VO+_BP_FIL") (class "Default")
      (node (ref "IC1") (pin "24") (pinfunction "VO+_BP_FIL_24") (pintype "output"))
      (node (ref "JP3") (pin "3") (pinfunction "3_3") (pintype "passive"))
    )
    (net (code "94") (name "/VO+_CH") (class "Default")
      (node (ref "IC1") (pin "50") (pinfunction "VO+_CH_50") (pintype "input"))
      (node (ref "JP13") (pin "3") (pinfunction "3_3") (pintype "passive"))
    )
    (net (code "95") (name "/VO+_FIL") (class "Default")
      (node (ref "IC1") (pin "30") (pinfunction "VO+_FIL_30") (pintype "output"))
      (node (ref "JP3") (pin "1") (pinfunction "1_1") (pintype "passive"))
    )
    (net (code "96") (name "/VO-_BP_FIL") (class "Default")
      (node (ref "IC1") (pin "25") (pinfunction "VO-_BP_FIL_25") (pintype "output"))
      (node (ref "JP18") (pin "3") (pinfunction "3_3") (pintype "passive"))
    )
    (net (code "97") (name "/VO-_CH") (class "Default")
      (node (ref "IC1") (pin "52") (pinfunction "VO-_CH_52") (pintype "input"))
      (node (ref "JP14") (pin "3") (pinfunction "3_3") (pintype "passive"))
    )
    (net (code "98") (name "/VO-_FIL") (class "Default")
      (node (ref "IC1") (pin "31") (pinfunction "VO-_FIL_31") (pintype "output"))
      (node (ref "JP18") (pin "1") (pinfunction "1_1") (pintype "passive"))
    )
    (net (code "99") (name "/VOCM") (class "Default")
      (node (ref "IC1") (pin "34") (pinfunction "VOCM_AUX_34") (pintype "input"))
      (node (ref "IC1") (pin "36") (pinfunction "VOCM_36") (pintype "input"))
      (node (ref "JP16") (pin "2") (pinfunction "2_2") (pintype "passive"))
      (node (ref "TP14") (pin "TP") (pinfunction "TP_TP") (pintype "input"))
    )
    (net (code "100") (name "/VOCM_1") (class "Default")
      (node (ref "C49") (pin "1") (pinfunction "1_1") (pintype "passive"))
      (node (ref "IC14") (pin "3") (pinfunction "+INA_3") (pintype "bidirectional"))
      (node (ref "IC2") (pin "4") (pinfunction "B_4") (pintype "bidirectional"))
      (node (ref "JP7") (pin "3") (pinfunction "3_3") (pintype "passive"))
      (node (ref "TP30") (pin "TP") (pinfunction "TP_TP") (pintype "input"))
    )
    (net (code "101") (name "/VOCM_BUFF") (class "Default")
      (node (ref "C33") (pin "1") (pinfunction "1_1") (pintype "passive"))
      (node (ref "IC12") (pin "6") (pinfunction "-INB_6") (pintype "bidirectional"))
      (node (ref "IC12") (pin "7") (pinfunction "OUTB_7") (pintype "bidirectional"))
      (node (ref "JP16") (pin "1") (pinfunction "1_1") (pintype "passive"))
    )
    (net (code "102") (name "/VOCM_MUX") (class "Default")
      (node (ref "C48") (pin "1") (pinfunction "1_1") (pintype "passive"))
      (node (ref "IC12") (pin "5") (pinfunction "+INB_5") (pintype "bidirectional"))
      (node (ref "IC4") (pin "4") (pinfunction "B_4") (pintype "bidirectional"))
      (node (ref "JP16") (pin "3") (pinfunction "3_3") (pintype "passive"))
      (node (ref "TP13") (pin "TP") (pinfunction "TP_TP") (pintype "input"))
    )
    (net (code "103") (name "/VOUT_CSA") (class "Default")
      (node (ref "IC1") (pin "54") (pinfunction "VOUT_CSA_54") (pintype "output"))
      (node (ref "JP19") (pin "3") (pinfunction "3_3") (pintype "passive"))
      (node (ref "TP9") (pin "TP") (pinfunction "TP_TP") (pintype "input"))
    )
    (net (code "104") (name "/VSS") (class "Default")
      (node (ref "IC12") (pin "4") (pinfunction "V-_4") (pintype "bidirectional"))
      (node (ref "IC14") (pin "4") (pinfunction "V-_4") (pintype "bidirectional"))
      (node (ref "JP17") (pin "4") (pinfunction "P$4_4") (pintype "bidirectional"))
      (node (ref "TP39") (pin "TP") (pinfunction "TP_TP") (pintype "input"))
    )
    (net (code "105") (name "/V_REF_PRECHAR") (class "Default")
      (node (ref "IC1") (pin "7") (pinfunction "V_REF_PRECHAR_7") (pintype "input"))
      (node (ref "JP7") (pin "2") (pinfunction "2_2") (pintype "passive"))
      (node (ref "TP37") (pin "TP") (pinfunction "TP_TP") (pintype "input"))
    )
    (net (code "106") (name "/V_REF_PRECHAR_BUFF") (class "Default")
      (node (ref "C34") (pin "1") (pinfunction "1_1") (pintype "passive"))
      (node (ref "IC14") (pin "1") (pinfunction "OUTA_1") (pintype "bidirectional"))
      (node (ref "IC14") (pin "2") (pinfunction "-INA_2") (pintype "bidirectional"))
      (node (ref "JP7") (pin "1") (pinfunction "1_1") (pintype "passive"))
    )
    (net (code "107") (name "/~{CS_ADC1}") (class "Default")
      (node (ref "IC22") (pin "P$9") (pinfunction "CNVST_P$9") (pintype "bidirectional"))
      (node (ref "J1") (pin "A44") (pinfunction "A44_A44") (pintype "bidirectional"))
    )
    (net (code "108") (name "/~{CS_ADC2}") (class "Default")
      (node (ref "J1") (pin "A15") (pinfunction "A15_A15") (pintype "bidirectional"))
      (node (ref "U$5") (pin "P$9") (pinfunction "CNVST_P$9") (pintype "bidirectional"))
    )
    (net (code "109") (name "/~{CS_DAC}") (class "Default")
      (node (ref "IC23") (pin "9") (pinfunction "~{SYNC}_9") (pintype "bidirectional"))
      (node (ref "J1") (pin "A17") (pinfunction "A17_A17") (pintype "bidirectional"))
    )
    (net (code "110") (name "Net-(C36-Pad2)") (class "Default")
      (node (ref "C36") (pin "2") (pinfunction "2_2") (pintype "passive"))
      (node (ref "C37") (pin "1") (pinfunction "1_1") (pintype "passive"))
      (node (ref "JP9") (pin "2") (pinfunction "2_2") (pintype "passive"))
    )
    (net (code "111") (name "Net-(C37-Pad2)") (class "Default")
      (node (ref "C37") (pin "2") (pinfunction "2_2") (pintype "passive"))
      (node (ref "JP10") (pin "1") (pinfunction "1_1") (pintype "passive"))
    )
    (net (code "112") (name "Net-(C38-Pad1)") (class "Default")
      (node (ref "C38") (pin "1") (pinfunction "1_1") (pintype "passive"))
      (node (ref "JP1") (pin "2") (pinfunction "2_2") (pintype "passive"))
    )
    (net (code "113") (name "Net-(C42-Pad1)") (class "Default")
      (node (ref "C42") (pin "1") (pinfunction "1_1") (pintype "passive"))
      (node (ref "J1") (pin "B50") (pinfunction "B50_B50") (pintype "bidirectional"))
      (node (ref "R8") (pin "2") (pinfunction "2_2") (pintype "passive"))
    )
    (net (code "114") (name "Net-(IC18-W)") (class "Default")
      (node (ref "IC18") (pin "1") (pinfunction "W_1") (pintype "bidirectional"))
      (node (ref "IC2") (pin "1") (pinfunction "A0_1") (pintype "bidirectional"))
    )
    (net (code "115") (name "Net-(IC19-W)") (class "Default")
      (node (ref "IC19") (pin "1") (pinfunction "W_1") (pintype "bidirectional"))
      (node (ref "IC3") (pin "1") (pinfunction "A0_1") (pintype "bidirectional"))
    )
    (net (code "116") (name "Net-(IC20-W)") (class "Default")
      (node (ref "IC20") (pin "1") (pinfunction "W_1") (pintype "bidirectional"))
      (node (ref "IC4") (pin "1") (pinfunction "A0_1") (pintype "bidirectional"))
    )
    (net (code "117") (name "Net-(J1-PadA46)") (class "Default")
      (node (ref "J1") (pin "A46") (pinfunction "A46_A46") (pintype "bidirectional"))
      (node (ref "J1") (pin "A48") (pinfunction "A48_A48") (pintype "bidirectional"))
    )
    (net (code "118") (name "Net-(J1-PadB1)") (class "Default")
      (node (ref "J1") (pin "B1") (pinfunction "B1_B1") (pintype "bidirectional"))
      (node (ref "R9") (pin "2") (pinfunction "2_2") (pintype "passive"))
    )
    (net (code "119") (name "unconnected-(IC5-N{slash}C-Pad1)") (class "Default")
      (node (ref "IC5") (pin "1") (pinfunction "N/C_1") (pintype "bidirectional"))
    )
    (net (code "120") (name "unconnected-(IC6-N{slash}C-Pad1)") (class "Default")
      (node (ref "IC6") (pin "1") (pinfunction "N/C_1") (pintype "bidirectional"))
    )
    (net (code "121") (name "unconnected-(IC7-N{slash}C-Pad1)") (class "Default")
      (node (ref "IC7") (pin "1") (pinfunction "N/C_1") (pintype "bidirectional"))
    )
    (net (code "122") (name "unconnected-(IC8-N{slash}C-Pad1)") (class "Default")
      (node (ref "IC8") (pin "1") (pinfunction "N/C_1") (pintype "bidirectional"))
    )
    (net (code "123") (name "unconnected-(IC9-GND-Pad4)") (class "Default")
      (node (ref "IC9") (pin "4") (pinfunction "GND_4") (pintype "passive"))
    )
    (net (code "124") (name "unconnected-(IC10-N{slash}C-Pad1)") (class "Default")
      (node (ref "IC10") (pin "1") (pinfunction "N/C_1") (pintype "bidirectional"))
    )
    (net (code "125") (name "unconnected-(IC11-GND-Pad4)") (class "Default")
      (node (ref "IC11") (pin "4") (pinfunction "GND_4") (pintype "passive"))
    )
    (net (code "126") (name "unconnected-(IC13-N{slash}C-Pad1)") (class "Default")
      (node (ref "IC13") (pin "1") (pinfunction "N/C_1") (pintype "bidirectional"))
    )
    (net (code "127") (name "unconnected-(IC14-+INB-Pad5)") (class "Default")
      (node (ref "IC14") (pin "5") (pinfunction "+INB_5") (pintype "bidirectional"))
    )
    (net (code "128") (name "unconnected-(IC14--INB-Pad6)") (class "Default")
      (node (ref "IC14") (pin "6") (pinfunction "-INB_6") (pintype "bidirectional"))
    )
    (net (code "129") (name "unconnected-(IC14-OUTB-Pad7)") (class "Default")
      (node (ref "IC14") (pin "7") (pinfunction "OUTB_7") (pintype "bidirectional"))
    )
    (net (code "130") (name "unconnected-(IC15-GND-Pad4)") (class "Default")
      (node (ref "IC15") (pin "4") (pinfunction "GND_4") (pintype "passive"))
    )
    (net (code "131") (name "unconnected-(IC16-N{slash}C-Pad1)") (class "Default")
      (node (ref "IC16") (pin "1") (pinfunction "N/C_1") (pintype "bidirectional"))
    )
    (net (code "132") (name "unconnected-(IC17-N{slash}C-Pad1)") (class "Default")
      (node (ref "IC17") (pin "1") (pinfunction "N/C_1") (pintype "bidirectional"))
    )
    (net (code "133") (name "unconnected-(J1-PadA1)") (class "Default")
      (node (ref "J1") (pin "A1") (pinfunction "A1_A1") (pintype "bidirectional"))
    )
    (net (code "134") (name "unconnected-(J1-PadA2)") (class "Default")
      (node (ref "J1") (pin "A2") (pinfunction "A2_A2") (pintype "bidirectional"))
    )
    (net (code "135") (name "unconnected-(J1-PadA3)") (class "Default")
      (node (ref "J1") (pin "A3") (pinfunction "A3_A3") (pintype "bidirectional"))
    )
    (net (code "136") (name "unconnected-(J1-PadA4)") (class "Default")
      (node (ref "J1") (pin "A4") (pinfunction "A4_A4") (pintype "bidirectional"))
    )
    (net (code "137") (name "unconnected-(J1-PadA5)") (class "Default")
      (node (ref "J1") (pin "A5") (pinfunction "A5_A5") (pintype "bidirectional"))
    )
    (net (code "138") (name "unconnected-(J1-PadA27)") (class "Default")
      (node (ref "J1") (pin "A27") (pinfunction "A27_A27") (pintype "bidirectional"))
    )
    (net (code "139") (name "unconnected-(J1-PadA29)") (class "Default")
      (node (ref "J1") (pin "A29") (pinfunction "A29_A29") (pintype "bidirectional"))
    )
    (net (code "140") (name "unconnected-(J1-PadA31)") (class "Default")
      (node (ref "J1") (pin "A31") (pinfunction "A31_A31") (pintype "bidirectional"))
    )
    (net (code "141") (name "unconnected-(J1-PadA37)") (class "Default")
      (node (ref "J1") (pin "A37") (pinfunction "A37_A37") (pintype "bidirectional"))
    )
    (net (code "142") (name "unconnected-(J1-PadA39)") (class "Default")
      (node (ref "J1") (pin "A39") (pinfunction "A39_A39") (pintype "bidirectional"))
    )
    (net (code "143") (name "unconnected-(J1-PadA41)") (class "Default")
      (node (ref "J1") (pin "A41") (pinfunction "A41_A41") (pintype "bidirectional"))
    )
    (net (code "144") (name "unconnected-(J1-PadA47)") (class "Default")
      (node (ref "J1") (pin "A47") (pinfunction "A47_A47") (pintype "bidirectional"))
    )
    (net (code "145") (name "unconnected-(J1-PadA49)") (class "Default")
      (node (ref "J1") (pin "A49") (pinfunction "A49_A49") (pintype "bidirectional"))
    )
    (net (code "146") (name "unconnected-(J1-PadA50)") (class "Default")
      (node (ref "J1") (pin "A50") (pinfunction "A50_A50") (pintype "bidirectional"))
    )
    (net (code "147") (name "unconnected-(J1-PadB3)") (class "Default")
      (node (ref "J1") (pin "B3") (pinfunction "B3_B3") (pintype "bidirectional"))
    )
    (net (code "148") (name "unconnected-(J1-PadB4)") (class "Default")
      (node (ref "J1") (pin "B4") (pinfunction "B4_B4") (pintype "bidirectional"))
    )
    (net (code "149") (name "unconnected-(J1-PadB46)") (class "Default")
      (node (ref "J1") (pin "B46") (pinfunction "B46_B46") (pintype "bidirectional"))
    )
    (net (code "150") (name "unconnected-(J1-PadB48)") (class "Default")
      (node (ref "J1") (pin "B48") (pinfunction "B48_B48") (pintype "bidirectional"))
    )
    (net (code "151") (name "unconnected-(J1-PadB49)") (class "Default")
      (node (ref "J1") (pin "B49") (pinfunction "B49_B49") (pintype "bidirectional"))
    )
  )
)
